# HLK-7621-ALL-KIT-V2_4.net
KiCad netlist of a schematic drawn in Altium Designer
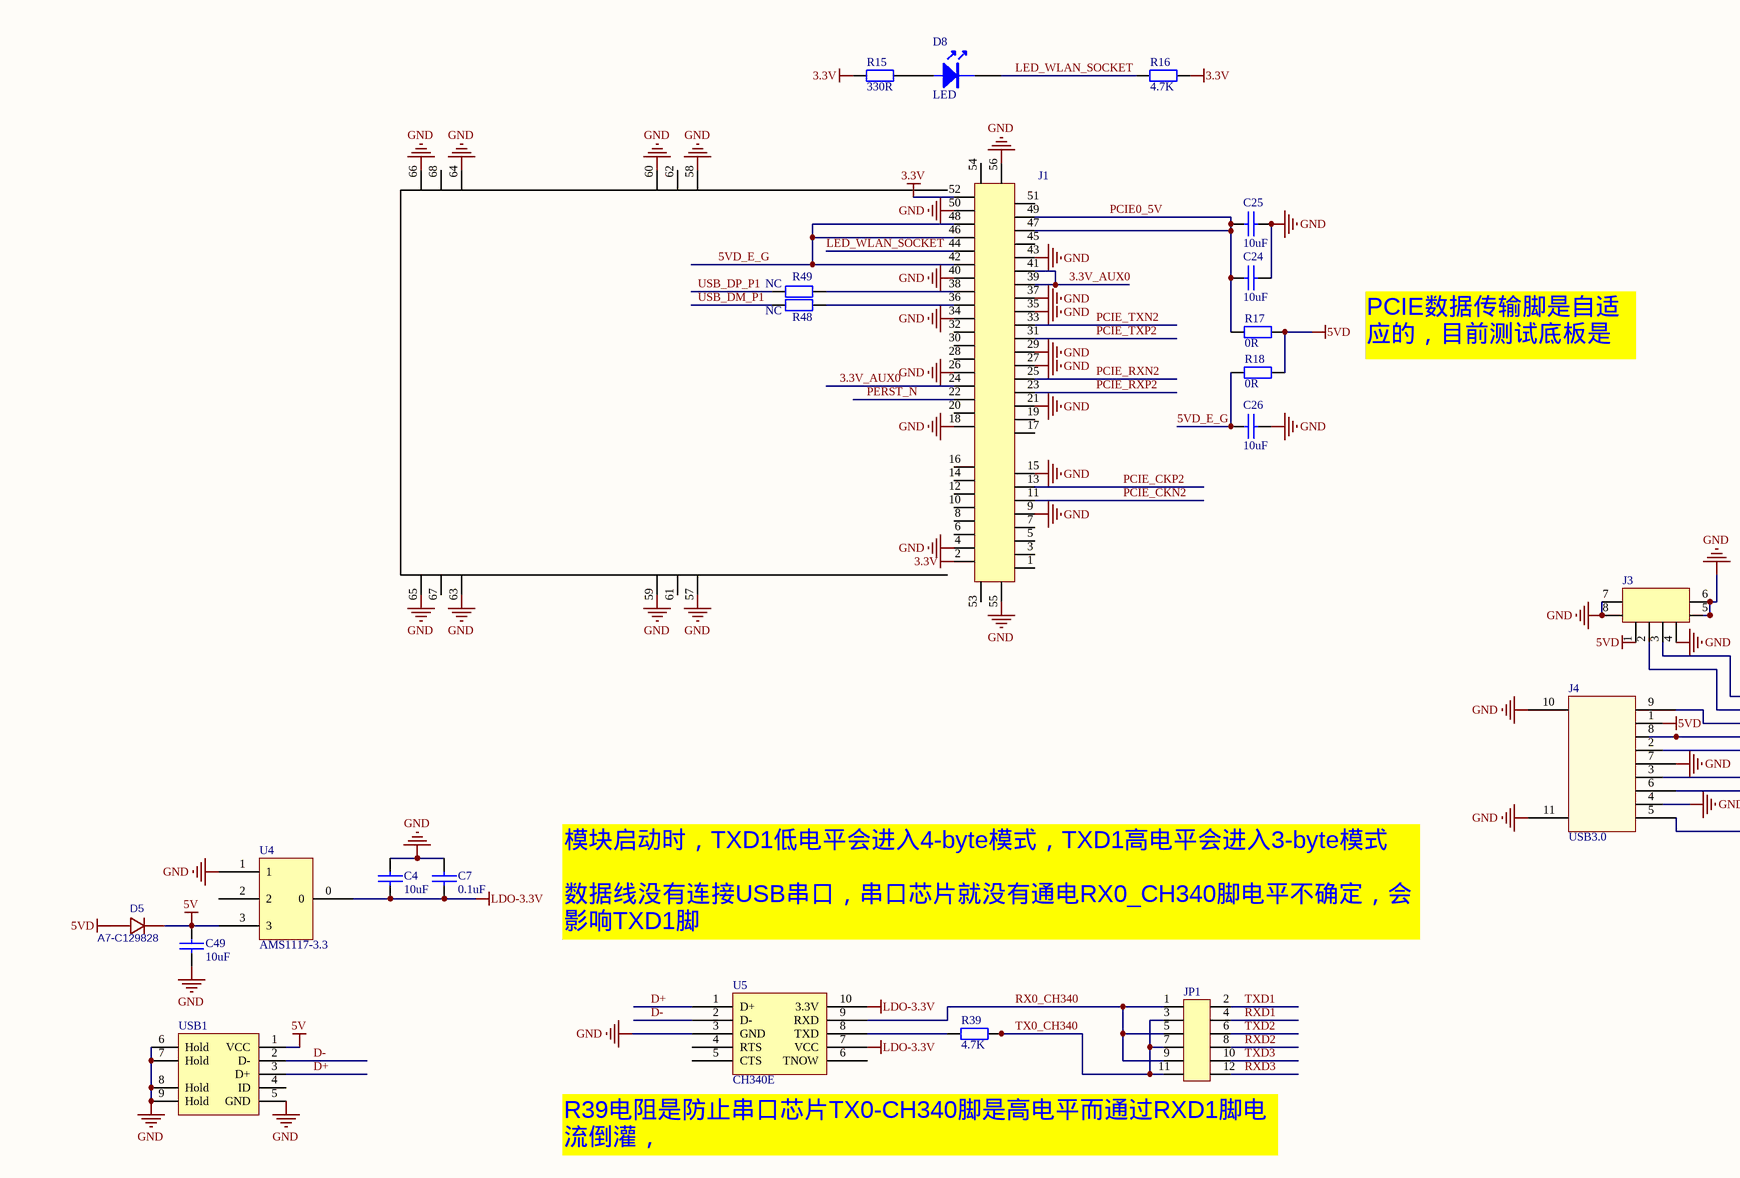
[diagram p0: HLK-7621-ALL-KIT-V2.4.SchDoc, top left]
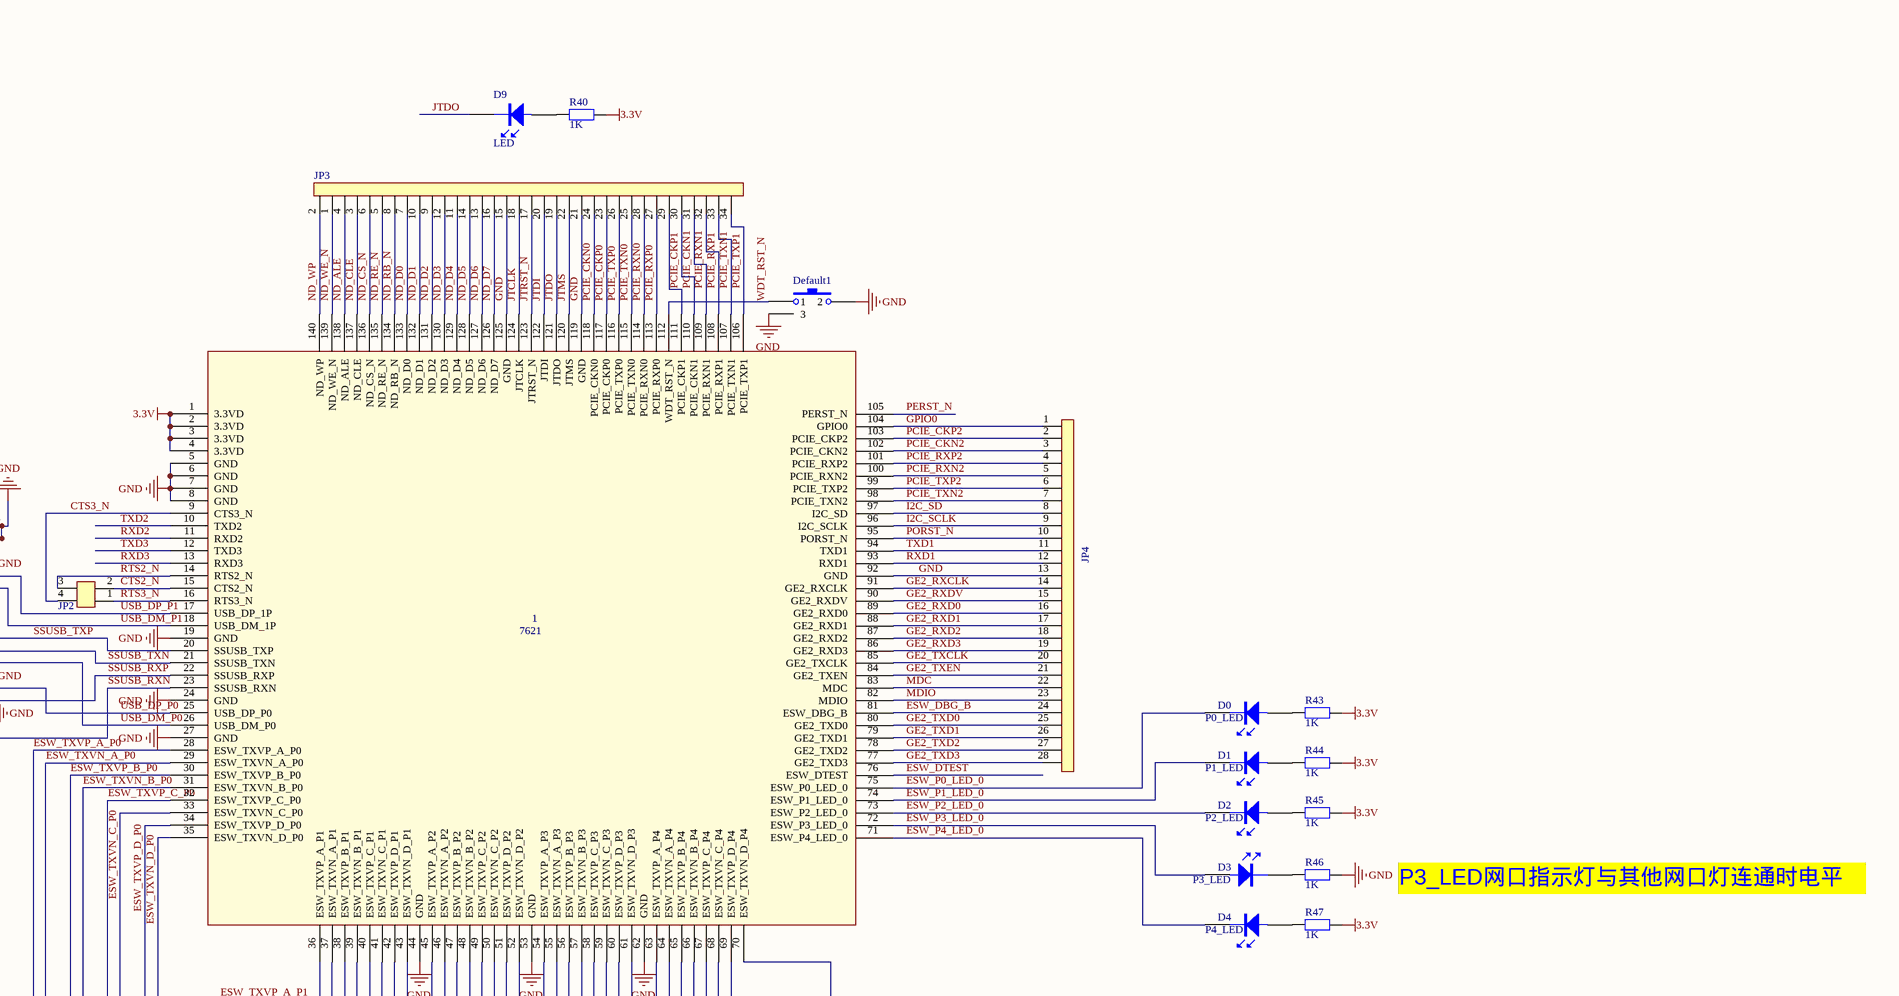
[diagram p1: HLK-7621-ALL-KIT-V2.4.SchDoc, top right]
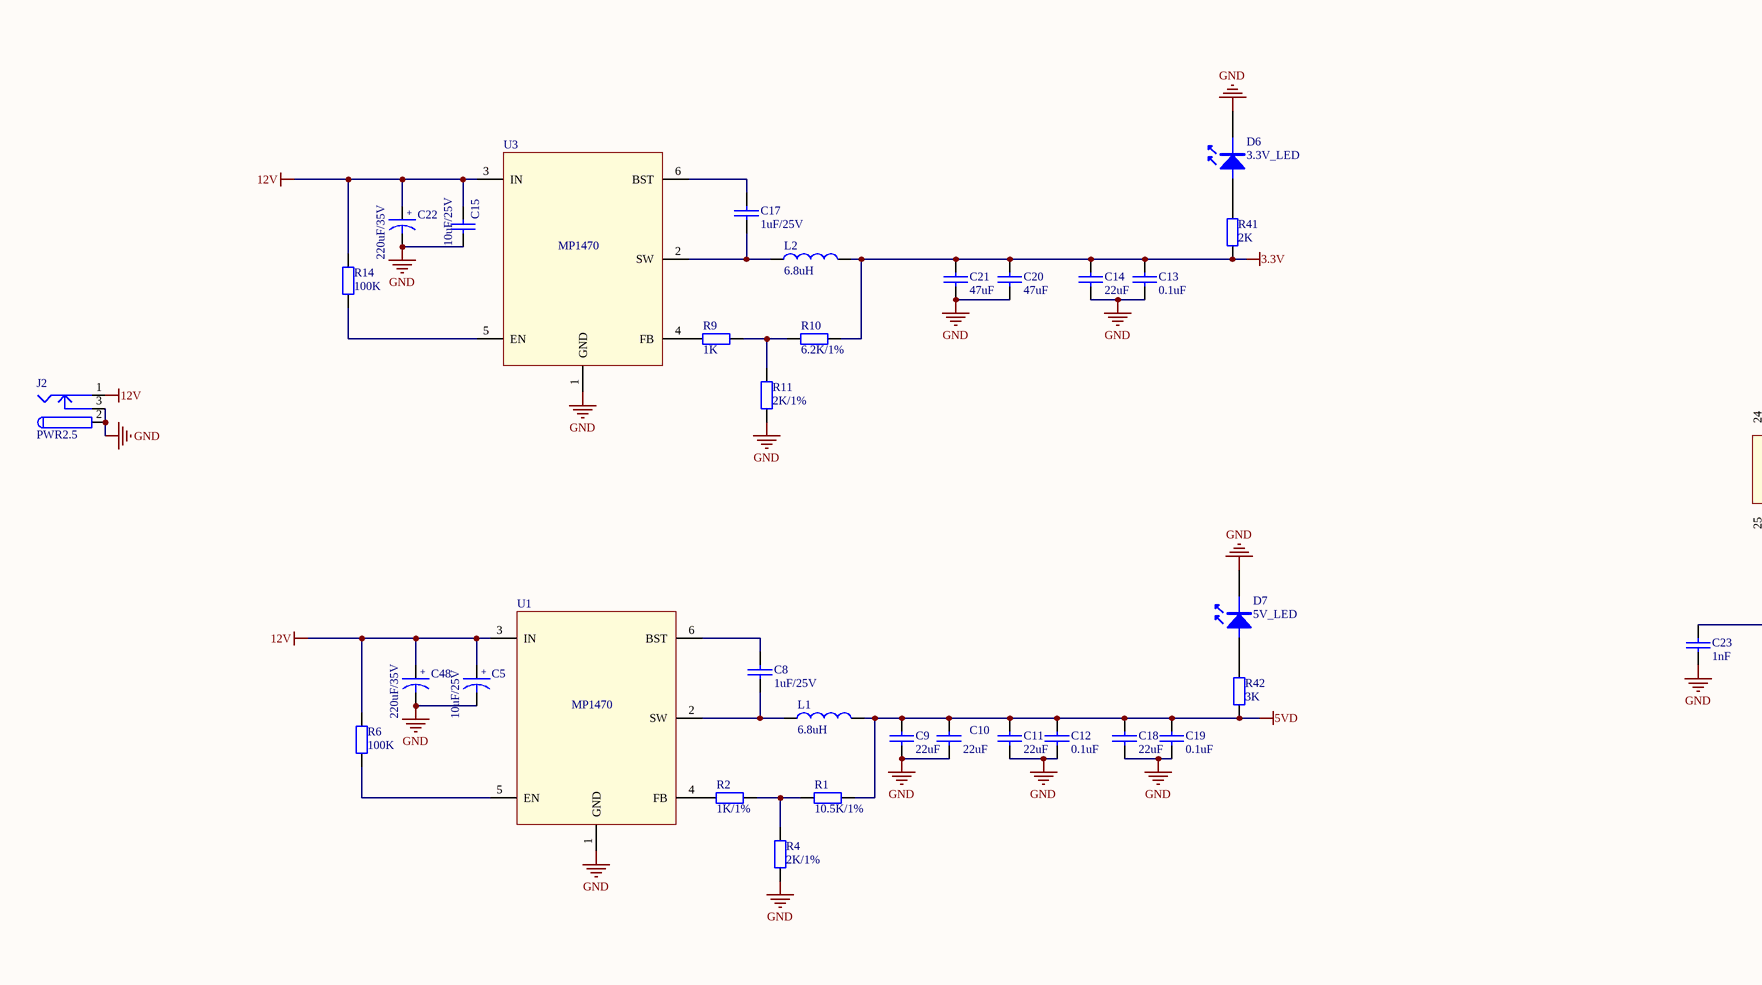
[diagram p2: HLK-7621-ALL-KIT-V2.4.SchDoc, bottom left]
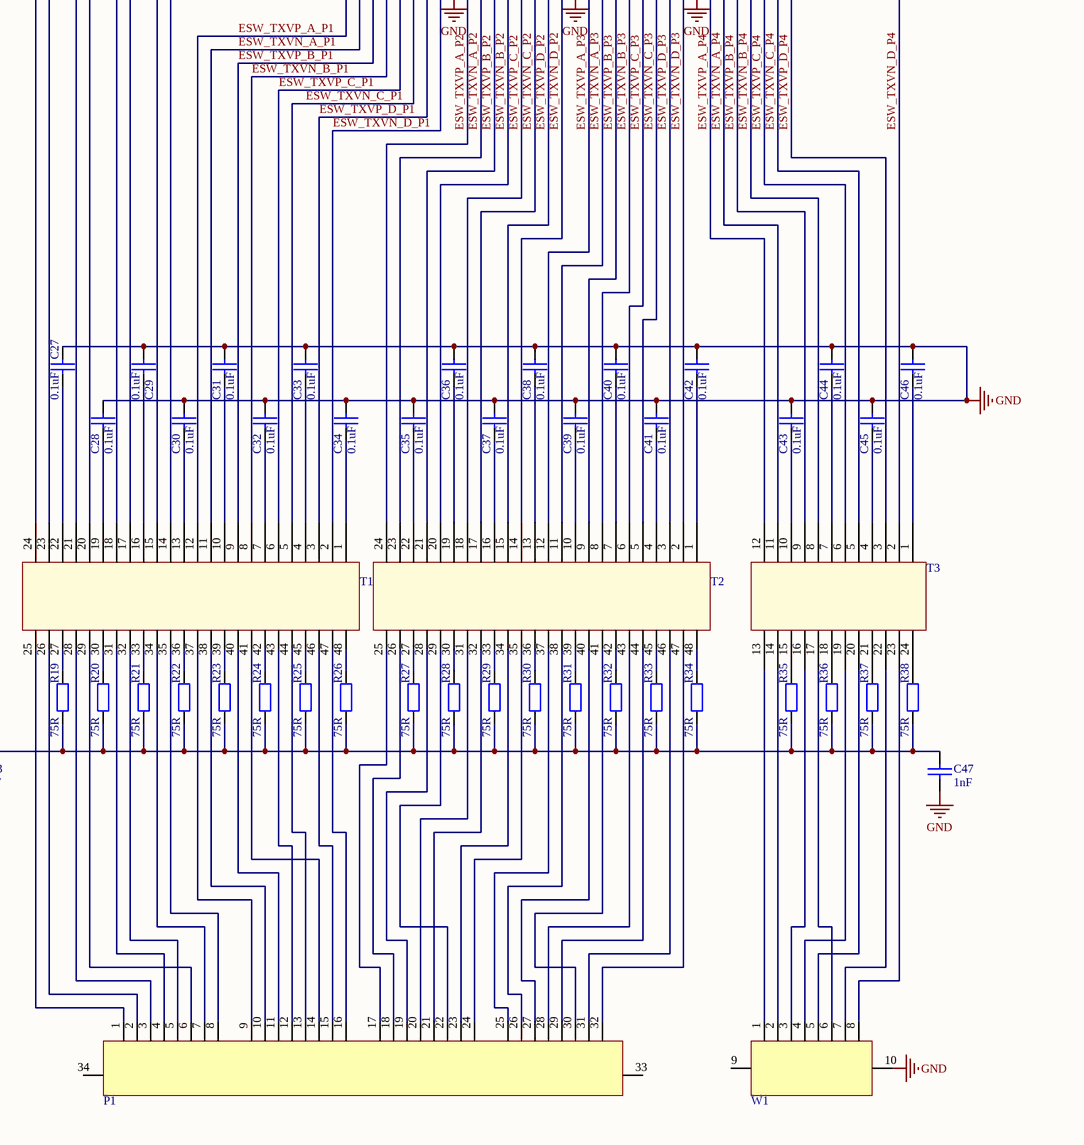
[diagram p3: HLK-7621-ALL-KIT-V2.4.SchDoc, bottom right]

(export (version "E")
  (design (tool "Eeschema 10.0.6"))
  (components
    (comp (ref "1") (value "7621") (footprint "HLK-7621") (libsource (lib "Schlib1") (part "7621")))
    (comp (ref "C4")
      (value "10uF")
      (footprint "0603")
      (description "Capacitor")
      (libsource (lib "*") (part "CAP"))
    )
    (comp (ref "C5")
      (value "10uF/25V")
      (footprint "L0805")
      (description "Capacitor")
      (libsource (lib "Miscellaneous Devices") (part "CAPACITOR POL"))
    )
    (comp (ref "C7")
      (value "0.1uF")
      (footprint "0603")
      (description "Capacitor")
      (libsource (lib "*") (part "CAP"))
    )
    (comp (ref "C8")
      (value "1uF/25V")
      (footprint "0603")
      (description "Capacitor")
      (libsource (lib "*") (part "CAP"))
    )
    (comp (ref "C9")
      (value "22uF")
      (footprint "0603")
      (description "Capacitor")
      (libsource (lib "*") (part "CAP"))
    )
    (comp (ref "C10")
      (value "22uF")
      (footprint "0603")
      (description "Capacitor")
      (libsource (lib "*") (part "CAP"))
    )
    (comp (ref "C11")
      (value "22uF")
      (footprint "0603")
      (description "Capacitor")
      (libsource (lib "*") (part "CAP"))
    )
    (comp (ref "C12")
      (value "0.1uF")
      (footprint "0603")
      (description "Capacitor")
      (libsource (lib "*") (part "CAP"))
    )
    (comp (ref "C13")
      (value "0.1uF")
      (footprint "0603")
      (description "Capacitor")
      (libsource (lib "*") (part "CAP"))
    )
    (comp (ref "C14")
      (value "22uF")
      (footprint "0603")
      (description "Capacitor")
      (libsource (lib "*") (part "CAP"))
    )
    (comp (ref "C15")
      (value "10uF/25V")
      (footprint "L0805")
      (description "Capacitor")
      (libsource (lib "*") (part "CAP"))
    )
    (comp (ref "C17")
      (value "1uF/25V")
      (footprint "0603")
      (description "Capacitor")
      (libsource (lib "*") (part "CAP"))
    )
    (comp (ref "C18")
      (value "22uF")
      (footprint "0603")
      (description "Capacitor")
      (libsource (lib "*") (part "CAP"))
    )
    (comp (ref "C19")
      (value "0.1uF")
      (footprint "0603")
      (description "Capacitor")
      (libsource (lib "*") (part "CAP"))
    )
    (comp (ref "C20")
      (value "47uF")
      (footprint "0603")
      (description "Capacitor")
      (libsource (lib "*") (part "CAP"))
    )
    (comp (ref "C21")
      (value "47uF")
      (footprint "0603")
      (description "Capacitor")
      (libsource (lib "*") (part "CAP"))
    )
    (comp (ref "C22")
      (value "220uF/35V")
      (footprint "CAP_SMT_8*10.5")
      (description "Capacitor")
      (libsource (lib "Miscellaneous Devices") (part "CAPACITOR POL"))
    )
    (comp (ref "C23")
      (value "1nF")
      (footprint "C1206")
      (description "Capacitor")
      (libsource (lib "*") (part "CAP"))
    )
    (comp (ref "C24")
      (value "10uF")
      (footprint "C1206")
      (description "Capacitor")
      (libsource (lib "*") (part "CAP"))
    )
    (comp (ref "C25")
      (value "10uF")
      (footprint "C1206")
      (description "Capacitor")
      (libsource (lib "*") (part "CAP"))
    )
    (comp (ref "C26")
      (value "10uF")
      (footprint "C1206")
      (description "Capacitor")
      (libsource (lib "*") (part "CAP"))
    )
    (comp (ref "C27")
      (value "0.1uF")
      (footprint "C0402")
      (description "Capacitor")
      (libsource (lib "*") (part "CAP"))
    )
    (comp (ref "C28")
      (value "0.1uF")
      (footprint "C0402")
      (description "Capacitor")
      (libsource (lib "*") (part "CAP"))
    )
    (comp (ref "C29")
      (value "0.1uF")
      (footprint "C0402")
      (description "Capacitor")
      (libsource (lib "*") (part "CAP"))
    )
    (comp (ref "C30")
      (value "0.1uF")
      (footprint "C0402")
      (description "Capacitor")
      (libsource (lib "*") (part "CAP"))
    )
    (comp (ref "C31")
      (value "0.1uF")
      (footprint "C0402")
      (description "Capacitor")
      (libsource (lib "*") (part "CAP"))
    )
    (comp (ref "C32")
      (value "0.1uF")
      (footprint "C0402")
      (description "Capacitor")
      (libsource (lib "*") (part "CAP"))
    )
    (comp (ref "C33")
      (value "0.1uF")
      (footprint "C0402")
      (description "Capacitor")
      (libsource (lib "*") (part "CAP"))
    )
    (comp (ref "C34")
      (value "0.1uF")
      (footprint "C0402")
      (description "Capacitor")
      (libsource (lib "*") (part "CAP"))
    )
    (comp (ref "C35")
      (value "0.1uF")
      (footprint "C0402")
      (description "Capacitor")
      (libsource (lib "*") (part "CAP"))
    )
    (comp (ref "C36")
      (value "0.1uF")
      (footprint "C0402")
      (description "Capacitor")
      (libsource (lib "*") (part "CAP"))
    )
    (comp (ref "C37")
      (value "0.1uF")
      (footprint "C0402")
      (description "Capacitor")
      (libsource (lib "*") (part "CAP"))
    )
    (comp (ref "C38")
      (value "0.1uF")
      (footprint "C0402")
      (description "Capacitor")
      (libsource (lib "*") (part "CAP"))
    )
    (comp (ref "C39")
      (value "0.1uF")
      (footprint "C0402")
      (description "Capacitor")
      (libsource (lib "*") (part "CAP"))
    )
    (comp (ref "C40")
      (value "0.1uF")
      (footprint "C0402")
      (description "Capacitor")
      (libsource (lib "*") (part "CAP"))
    )
    (comp (ref "C41")
      (value "0.1uF")
      (footprint "C0402")
      (description "Capacitor")
      (libsource (lib "*") (part "CAP"))
    )
    (comp (ref "C42")
      (value "0.1uF")
      (footprint "C0402")
      (description "Capacitor")
      (libsource (lib "*") (part "CAP"))
    )
    (comp (ref "C43")
      (value "0.1uF")
      (footprint "C0402")
      (description "Capacitor")
      (libsource (lib "*") (part "CAP"))
    )
    (comp (ref "C44")
      (value "0.1uF")
      (footprint "C0402")
      (description "Capacitor")
      (libsource (lib "*") (part "CAP"))
    )
    (comp (ref "C45")
      (value "0.1uF")
      (footprint "C0402")
      (description "Capacitor")
      (libsource (lib "*") (part "CAP"))
    )
    (comp (ref "C46")
      (value "0.1uF")
      (footprint "C0402")
      (description "Capacitor")
      (libsource (lib "*") (part "CAP"))
    )
    (comp (ref "C47")
      (value "1nF")
      (footprint "C1206")
      (description "Capacitor")
      (libsource (lib "*") (part "CAP"))
    )
    (comp (ref "C48")
      (value "220uF/35V")
      (footprint "CAP_SMT_8*10.5")
      (description "Capacitor")
      (libsource (lib "Miscellaneous Devices") (part "CAPACITOR POL"))
    )
    (comp (ref "C49")
      (value "10uF")
      (footprint "0603")
      (description "Capacitor")
      (libsource (lib "*") (part "CAP"))
    )
    (comp (ref "D0") (value "P0_LED") (footprint "0603LED") (libsource (lib "*") (part "LED")))
    (comp (ref "D1") (value "P1_LED") (footprint "0603LED") (libsource (lib "*") (part "LED")))
    (comp (ref "D2") (value "P2_LED") (footprint "0603LED") (libsource (lib "*") (part "LED")))
    (comp (ref "D3") (value "P3_LED") (footprint "0603LED") (libsource (lib "*") (part "LED")))
    (comp (ref "D4") (value "P4_LED") (footprint "0603LED") (libsource (lib "*") (part "LED")))
    (comp (ref "D5")
      (value "A7-C129828")
      (footprint "SOD-123F_L2.8-W1.8-LS3.7-RD")
      (fields (field (name "BOM_SUPPLIER PART") "C129828") (field (name "CONTRIBUTOR") "LCSC"))
      (libsource (lib "altium-import") (part "root_2_A7-C129828_"))
    )
    (comp (ref "D6") (value "3.3V_LED") (footprint "0603LED") (libsource (lib "*") (part "LED")))
    (comp (ref "D7") (value "5V_LED") (footprint "0603LED") (libsource (lib "*") (part "LED")))
    (comp (ref "D8") (value "LED") (footprint "0603LED") (libsource (lib "") (part "LED_1")))
    (comp (ref "D9") (value "LED") (footprint "0603LED") (libsource (lib "*") (part "LED")))
    (comp (ref "Default1")
      (value "SW-PB")
      (footprint "K5")
      (description "Switch")
      (fields (field (name "PUBLISHER") "Altium Limited"))
      (libsource (lib "Miscellaneous Devices") (part "SW-PB"))
    )
    (comp (ref "J1")
      (value "~")
      (footprint "CONSG/54/MINICARD/AS0B22-S68-7F/HALF/FUL")
      (libsource (lib "") (part "Component_1_2"))
    )
    (comp (ref "J2")
      (value "PWR2.5")
      (description "Low Voltage Power Supply Connector")
      (fields (field (name "PUBLISHER") "Altium Limited"))
      (libsource (lib "*") (part "PWR2.5"))
    )
    (comp (ref "J3") (value "~") (libsource (lib "") (part "2_1")))
    (comp (ref "J4") (value "USB3.0") (libsource (lib "Schlib1") (part "USB3.0/9P/DIP/MAINSUPER")))
    (comp (ref "JP1") (value "~") (footprint "HDR2X6") (libsource (lib "Schlib1") (part "Component_1")))
    (comp (ref "JP2") (value "~") (footprint "HDR2X2") (libsource (lib "") (part "2_2")))
    (comp (ref "JP3") (value "~") (footprint "HDR2X17") (libsource (lib "Schlib1") (part "2")))
    (comp (ref "JP4") (value "2") (footprint "HDR2X17") (libsource (lib "") (part "2_3")))
    (comp (ref "L1")
      (value "6.8uH")
      (footprint "4.7uH SMD,5.8x5.2x4.5mm")
      (libsource (lib "ARM9") (part "INDUCTOR1"))
    )
    (comp (ref "L2")
      (value "6.8uH")
      (footprint "4.7uH SMD,5.8x5.2x4.5mm")
      (libsource (lib "ARM9") (part "INDUCTOR1"))
    )
    (comp (ref "P1")
      (value "Component_2")
      (footprint "PHJ8X4_N")
      (libsource (lib "Schlib1") (part "Component_2"))
    )
    (comp (ref "R1")
      (value "10.5K/1%")
      (footprint "0603")
      (description "Resistor")
      (fields (field (name "PUBLISHER") "Altium Limited"))
      (libsource (lib "Miscellaneous Devices") (part "Res2"))
    )
    (comp (ref "R2")
      (value "1K/1%")
      (footprint "0603")
      (description "Resistor")
      (fields (field (name "PUBLISHER") "Altium Limited"))
      (libsource (lib "Miscellaneous Devices") (part "Res2"))
    )
    (comp (ref "R4")
      (value "2K/1%")
      (footprint "0603")
      (description "Resistor")
      (fields (field (name "PUBLISHER") "Altium Limited"))
      (libsource (lib "") (part "Res2_1"))
    )
    (comp (ref "R6")
      (value "100K")
      (footprint "0603")
      (description "Resistor")
      (fields (field (name "PUBLISHER") "Altium Limited"))
      (libsource (lib "") (part "Res2_1"))
    )
    (comp (ref "R9")
      (value "1K")
      (footprint "0603")
      (description "Resistor")
      (fields (field (name "PUBLISHER") "Altium Limited"))
      (libsource (lib "Miscellaneous Devices") (part "Res2"))
    )
    (comp (ref "R10")
      (value "6.2K/1%")
      (footprint "0603")
      (description "Resistor")
      (fields (field (name "PUBLISHER") "Altium Limited"))
      (libsource (lib "Miscellaneous Devices") (part "Res2"))
    )
    (comp (ref "R11")
      (value "2K/1%")
      (footprint "0603")
      (description "Resistor")
      (fields (field (name "PUBLISHER") "Altium Limited"))
      (libsource (lib "") (part "Res2_1"))
    )
    (comp (ref "R14")
      (value "100K")
      (footprint "0603")
      (description "Resistor")
      (fields (field (name "PUBLISHER") "Altium Limited"))
      (libsource (lib "") (part "Res2_1"))
    )
    (comp (ref "R15")
      (value "330R")
      (footprint "0603")
      (description "Resistor")
      (fields (field (name "PUBLISHER") "Altium Limited"))
      (libsource (lib "Miscellaneous Devices") (part "Res2"))
    )
    (comp (ref "R16")
      (value "4.7K")
      (footprint "0603")
      (description "Resistor")
      (fields (field (name "PUBLISHER") "Altium Limited"))
      (libsource (lib "Miscellaneous Devices") (part "Res2"))
    )
    (comp (ref "R17")
      (value "0R")
      (footprint "L0805")
      (description "Resistor")
      (fields (field (name "PUBLISHER") "Altium Limited"))
      (libsource (lib "") (part "Res2_2"))
    )
    (comp (ref "R18")
      (value "0R")
      (footprint "R1206")
      (description "Resistor")
      (fields (field (name "PUBLISHER") "Altium Limited"))
      (libsource (lib "Miscellaneous Devices") (part "Res2"))
    )
    (comp (ref "R19")
      (value "75R")
      (footprint "R0402")
      (description "Resistor")
      (fields (field (name "PUBLISHER") "Altium Limited"))
      (libsource (lib "Schlib1") (part "Res2"))
    )
    (comp (ref "R20")
      (value "75R")
      (footprint "R0402")
      (description "Resistor")
      (fields (field (name "PUBLISHER") "Altium Limited"))
      (libsource (lib "Schlib1") (part "Res2"))
    )
    (comp (ref "R21")
      (value "75R")
      (footprint "R0402")
      (description "Resistor")
      (fields (field (name "PUBLISHER") "Altium Limited"))
      (libsource (lib "Schlib1") (part "Res2"))
    )
    (comp (ref "R22")
      (value "75R")
      (footprint "R0402")
      (description "Resistor")
      (fields (field (name "PUBLISHER") "Altium Limited"))
      (libsource (lib "Schlib1") (part "Res2"))
    )
    (comp (ref "R23")
      (value "75R")
      (footprint "R0402")
      (description "Resistor")
      (fields (field (name "PUBLISHER") "Altium Limited"))
      (libsource (lib "Schlib1") (part "Res2"))
    )
    (comp (ref "R24")
      (value "75R")
      (footprint "R0402")
      (description "Resistor")
      (fields (field (name "PUBLISHER") "Altium Limited"))
      (libsource (lib "Schlib1") (part "Res2"))
    )
    (comp (ref "R25")
      (value "75R")
      (footprint "R0402")
      (description "Resistor")
      (fields (field (name "PUBLISHER") "Altium Limited"))
      (libsource (lib "Schlib1") (part "Res2"))
    )
    (comp (ref "R26")
      (value "75R")
      (footprint "R0402")
      (description "Resistor")
      (fields (field (name "PUBLISHER") "Altium Limited"))
      (libsource (lib "Schlib1") (part "Res2"))
    )
    (comp (ref "R27")
      (value "75R")
      (footprint "R0402")
      (description "Resistor")
      (fields (field (name "PUBLISHER") "Altium Limited"))
      (libsource (lib "Schlib1") (part "Res2"))
    )
    (comp (ref "R28")
      (value "75R")
      (footprint "R0402")
      (description "Resistor")
      (fields (field (name "PUBLISHER") "Altium Limited"))
      (libsource (lib "Schlib1") (part "Res2"))
    )
    (comp (ref "R29")
      (value "75R")
      (footprint "R0402")
      (description "Resistor")
      (fields (field (name "PUBLISHER") "Altium Limited"))
      (libsource (lib "Schlib1") (part "Res2"))
    )
    (comp (ref "R30")
      (value "75R")
      (footprint "R0402")
      (description "Resistor")
      (fields (field (name "PUBLISHER") "Altium Limited"))
      (libsource (lib "Schlib1") (part "Res2"))
    )
    (comp (ref "R31")
      (value "75R")
      (footprint "R0402")
      (description "Resistor")
      (fields (field (name "PUBLISHER") "Altium Limited"))
      (libsource (lib "Schlib1") (part "Res2"))
    )
    (comp (ref "R32")
      (value "75R")
      (footprint "R0402")
      (description "Resistor")
      (fields (field (name "PUBLISHER") "Altium Limited"))
      (libsource (lib "Schlib1") (part "Res2"))
    )
    (comp (ref "R33")
      (value "75R")
      (footprint "R0402")
      (description "Resistor")
      (fields (field (name "PUBLISHER") "Altium Limited"))
      (libsource (lib "Schlib1") (part "Res2"))
    )
    (comp (ref "R34")
      (value "75R")
      (footprint "R0402")
      (description "Resistor")
      (fields (field (name "PUBLISHER") "Altium Limited"))
      (libsource (lib "Schlib1") (part "Res2"))
    )
    (comp (ref "R35")
      (value "75R")
      (footprint "R0402")
      (description "Resistor")
      (fields (field (name "PUBLISHER") "Altium Limited"))
      (libsource (lib "Schlib1") (part "Res2"))
    )
    (comp (ref "R36")
      (value "75R")
      (footprint "R0402")
      (description "Resistor")
      (fields (field (name "PUBLISHER") "Altium Limited"))
      (libsource (lib "Schlib1") (part "Res2"))
    )
    (comp (ref "R37")
      (value "75R")
      (footprint "R0402")
      (description "Resistor")
      (fields (field (name "PUBLISHER") "Altium Limited"))
      (libsource (lib "Schlib1") (part "Res2"))
    )
    (comp (ref "R38")
      (value "75R")
      (footprint "R0402")
      (description "Resistor")
      (fields (field (name "PUBLISHER") "Altium Limited"))
      (libsource (lib "Schlib1") (part "Res2"))
    )
    (comp (ref "R39")
      (value "4.7K")
      (footprint "0603")
      (description "Resistor")
      (fields (field (name "PUBLISHER") "Altium Limited"))
      (libsource (lib "") (part "Res2_2"))
    )
    (comp (ref "R40")
      (value "1K")
      (footprint "0603")
      (description "Resistor")
      (fields (field (name "PUBLISHER") "Altium Limited"))
      (libsource (lib "Miscellaneous Devices") (part "Res2"))
    )
    (comp (ref "R41")
      (value "2K")
      (footprint "0603")
      (description "Resistor")
      (fields (field (name "PUBLISHER") "Altium Limited"))
      (libsource (lib "") (part "Res2_1"))
    )
    (comp (ref "R42")
      (value "3K")
      (footprint "0603")
      (description "Resistor")
      (fields (field (name "PUBLISHER") "Altium Limited"))
      (libsource (lib "") (part "Res2_1"))
    )
    (comp (ref "R43")
      (value "1K")
      (footprint "0603")
      (description "Resistor")
      (fields (field (name "PUBLISHER") "Altium Limited"))
      (libsource (lib "Miscellaneous Devices") (part "Res2"))
    )
    (comp (ref "R44")
      (value "1K")
      (footprint "0603")
      (description "Resistor")
      (fields (field (name "PUBLISHER") "Altium Limited"))
      (libsource (lib "Miscellaneous Devices") (part "Res2"))
    )
    (comp (ref "R45")
      (value "1K")
      (footprint "0603")
      (description "Resistor")
      (fields (field (name "PUBLISHER") "Altium Limited"))
      (libsource (lib "Miscellaneous Devices") (part "Res2"))
    )
    (comp (ref "R46")
      (value "1K")
      (footprint "0603")
      (description "Resistor")
      (fields (field (name "PUBLISHER") "Altium Limited"))
      (libsource (lib "Miscellaneous Devices") (part "Res2"))
    )
    (comp (ref "R47")
      (value "1K")
      (footprint "0603")
      (description "Resistor")
      (fields (field (name "PUBLISHER") "Altium Limited"))
      (libsource (lib "Miscellaneous Devices") (part "Res2"))
    )
    (comp (ref "R48")
      (value "NC")
      (footprint "0603")
      (description "Resistor")
      (fields (field (name "PUBLISHER") "Altium Limited"))
      (libsource (lib "Miscellaneous Devices") (part "Res2"))
    )
    (comp (ref "R49")
      (value "NC")
      (footprint "0603")
      (description "Resistor")
      (fields (field (name "PUBLISHER") "Altium Limited"))
      (libsource (lib "Miscellaneous Devices") (part "Res2"))
    )
    (comp (ref "T1")
      (value "HN4824CG")
      (footprint "TRANSFORMER/48P/SMD/GS5014LF")
      (libsource (lib "Schlib1") (part "TRANSFORMER/24P/SMD/HN2429CG"))
    )
    (comp (ref "T2")
      (value "HN4824CG")
      (footprint "TRANSFORMER/48P/SMD/GS5014LF")
      (libsource (lib "Schlib1") (part "TRANSFORMER/24P/SMD/HN2429CG"))
    )
    (comp (ref "T3")
      (value "HN2409CG")
      (footprint "TRANSFORMER/24P/SMD/HN2429CG")
      (libsource (lib "") (part "TRANSFORMER/24P/SMD/HN2429CG_1"))
    )
    (comp (ref "U1") (value "MP1470") (footprint "MP1470") (libsource (lib "原理图库") (part "MP1470")))
    (comp (ref "U3") (value "MP1470") (footprint "MP1470") (libsource (lib "原理图库") (part "MP1470")))
    (comp (ref "U4") (value "AMS1117-3.3") (footprint "1117") (libsource (lib "") (part "Component_1_1")))
    (comp (ref "U5") (value "CH340E") (footprint "MSOP-10") (libsource (lib "Schlib1") (part "CH340E")))
    (comp (ref "USB1") (value "USB1") (libsource (lib "Schlib1") (part "USB-B")))
    (comp (ref "W1")
      (value "Component_3")
      (footprint "PCBComponent_1")
      (libsource (lib "Schlib1") (part "Component_3"))
    )
  )
  (nets
    (net (code "1") (name "/3.3V_AUX0") (class "Default")
      (node (ref "J1") (pin "24") (pinfunction "24_24") (pintype "passive"))
      (node (ref "J1") (pin "39") (pinfunction "39_39") (pintype "passive"))
      (node (ref "J1") (pin "41") (pinfunction "41_41") (pintype "passive"))
    )
    (net (code "2") (name "/5VD_E_G") (class "Default")
      (node (ref "C26") (pin "1") (pinfunction "1_1") (pintype "passive"))
      (node (ref "J1") (pin "42") (pinfunction "42_42") (pintype "passive"))
      (node (ref "J1") (pin "46") (pinfunction "46_46") (pintype "passive"))
      (node (ref "J1") (pin "48") (pinfunction "48_48") (pintype "passive"))
      (node (ref "R18") (pin "2") (pinfunction "2_2") (pintype "passive"))
    )
    (net (code "3") (name "/CTS2_N") (class "Default")
      (node (ref "1") (pin "15") (pinfunction "CTS2_N_15") (pintype "passive"))
      (node (ref "JP2") (pin "2") (pinfunction "2_2") (pintype "passive"))
    )
    (net (code "4") (name "/CTS3_N") (class "Default")
      (node (ref "1") (pin "9") (pinfunction "CTS3_N_9") (pintype "passive"))
      (node (ref "JP2") (pin "4") (pinfunction "4_4") (pintype "passive"))
    )
    (net (code "5") (name "/D+") (class "Default")
      (node (ref "U5") (pin "1") (pinfunction "D+_1") (pintype "passive"))
      (node (ref "USB1") (pin "3") (pinfunction "D+_3") (pintype "passive"))
    )
    (net (code "6") (name "/D-") (class "Default")
      (node (ref "U5") (pin "2") (pinfunction "D-_2") (pintype "passive"))
      (node (ref "USB1") (pin "2") (pinfunction "D-_2") (pintype "passive"))
    )
    (net (code "7") (name "/ESW_DBG_B") (class "Default")
      (node (ref "1") (pin "81") (pinfunction "ESW_DBG_B_81") (pintype "passive"))
      (node (ref "JP4") (pin "24") (pinfunction "24_24") (pintype "passive"))
    )
    (net (code "8") (name "/ESW_DTEST") (class "Default")
      (node (ref "1") (pin "76") (pinfunction "ESW_DTEST_76") (pintype "passive"))
    )
    (net (code "9") (name "/ESW_P0_LED_0") (class "Default")
      (node (ref "1") (pin "75") (pinfunction "ESW_P0_LED_0_75") (pintype "passive"))
      (node (ref "D0") (pin "2") (pinfunction "2_2") (pintype "passive"))
    )
    (net (code "10") (name "/ESW_P1_LED_0") (class "Default")
      (node (ref "1") (pin "74") (pinfunction "ESW_P1_LED_0_74") (pintype "passive"))
      (node (ref "D1") (pin "2") (pinfunction "2_2") (pintype "passive"))
    )
    (net (code "11") (name "/ESW_P2_LED_0") (class "Default")
      (node (ref "1") (pin "73") (pinfunction "ESW_P2_LED_0_73") (pintype "passive"))
      (node (ref "D2") (pin "2") (pinfunction "2_2") (pintype "passive"))
    )
    (net (code "12") (name "/ESW_P3_LED_0") (class "Default")
      (node (ref "1") (pin "72") (pinfunction "ESW_P3_LED_0_72") (pintype "passive"))
      (node (ref "D3") (pin "1") (pinfunction "1_1") (pintype "passive"))
    )
    (net (code "13") (name "/ESW_P4_LED_0") (class "Default")
      (node (ref "1") (pin "71") (pinfunction "ESW_P4_LED_0_71") (pintype "passive"))
      (node (ref "D4") (pin "2") (pinfunction "2_2") (pintype "passive"))
    )
    (net (code "14") (name "/ESW_TXVN_A_P0") (class "Default")
      (node (ref "1") (pin "29") (pinfunction "ESW_TXVN_A_P0_29") (pintype "passive"))
      (node (ref "T1") (pin "23") (pinfunction "23_23") (pintype "passive"))
    )
    (net (code "15") (name "/ESW_TXVN_A_P1") (class "Default")
      (node (ref "1") (pin "37") (pinfunction "ESW_TXVN_A_P1_37") (pintype "passive"))
      (node (ref "T1") (pin "11") (pinfunction "11_11") (pintype "passive"))
    )
    (net (code "16") (name "/ESW_TXVN_A_P2") (class "Default")
      (node (ref "1") (pin "46") (pinfunction "ESW_TXVN_A_P2_46") (pintype "passive"))
      (node (ref "T2") (pin "23") (pinfunction "23_23") (pintype "passive"))
    )
    (net (code "17") (name "/ESW_TXVN_A_P3") (class "Default")
      (node (ref "1") (pin "55") (pinfunction "ESW_TXVN_A_P3_55") (pintype "passive"))
      (node (ref "T2") (pin "11") (pinfunction "11_11") (pintype "passive"))
    )
    (net (code "18") (name "/ESW_TXVN_A_P4") (class "Default")
      (node (ref "1") (pin "64") (pinfunction "ESW_TXVN_A_P4_64") (pintype "passive"))
      (node (ref "T3") (pin "11") (pinfunction "11_11") (pintype "passive"))
    )
    (net (code "19") (name "/ESW_TXVN_B_P0") (class "Default")
      (node (ref "1") (pin "31") (pinfunction "ESW_TXVN_B_P0_31") (pintype "passive"))
      (node (ref "T1") (pin "20") (pinfunction "20_20") (pintype "passive"))
    )
    (net (code "20") (name "/ESW_TXVN_B_P1") (class "Default")
      (node (ref "1") (pin "39") (pinfunction "ESW_TXVN_B_P1_39") (pintype "passive"))
      (node (ref "T1") (pin "8") (pinfunction "8_8") (pintype "passive"))
    )
    (net (code "21") (name "/ESW_TXVN_B_P2") (class "Default")
      (node (ref "1") (pin "48") (pinfunction "ESW_TXVN_B_P2_48") (pintype "passive"))
      (node (ref "T2") (pin "20") (pinfunction "20_20") (pintype "passive"))
    )
    (net (code "22") (name "/ESW_TXVN_B_P3") (class "Default")
      (node (ref "1") (pin "57") (pinfunction "ESW_TXVN_B_P3_57") (pintype "passive"))
      (node (ref "T2") (pin "8") (pinfunction "8_8") (pintype "passive"))
    )
    (net (code "23") (name "/ESW_TXVN_B_P4") (class "Default")
      (node (ref "1") (pin "66") (pinfunction "ESW_TXVN_B_P4_66") (pintype "passive"))
      (node (ref "T3") (pin "8") (pinfunction "8_8") (pintype "passive"))
    )
    (net (code "24") (name "/ESW_TXVN_C_P0") (class "Default")
      (node (ref "1") (pin "33") (pinfunction "ESW_TXVN_C_P0_33") (pintype "passive"))
      (node (ref "T1") (pin "17") (pinfunction "17_17") (pintype "passive"))
    )
    (net (code "25") (name "/ESW_TXVN_C_P1") (class "Default")
      (node (ref "1") (pin "41") (pinfunction "ESW_TXVN_C_P1_41") (pintype "passive"))
      (node (ref "T1") (pin "5") (pinfunction "5_5") (pintype "passive"))
    )
    (net (code "26") (name "/ESW_TXVN_C_P2") (class "Default")
      (node (ref "1") (pin "50") (pinfunction "ESW_TXVN_C_P2_50") (pintype "passive"))
      (node (ref "T2") (pin "17") (pinfunction "17_17") (pintype "passive"))
    )
    (net (code "27") (name "/ESW_TXVN_C_P3") (class "Default")
      (node (ref "1") (pin "59") (pinfunction "ESW_TXVN_C_P3_59") (pintype "passive"))
      (node (ref "T2") (pin "5") (pinfunction "5_5") (pintype "passive"))
    )
    (net (code "28") (name "/ESW_TXVN_C_P4") (class "Default")
      (node (ref "1") (pin "68") (pinfunction "ESW_TXVN_C_P4_68") (pintype "passive"))
      (node (ref "T3") (pin "5") (pinfunction "5_5") (pintype "passive"))
    )
    (net (code "29") (name "/ESW_TXVN_D_P0") (class "Default")
      (node (ref "1") (pin "35") (pinfunction "ESW_TXVN_D_P0_35") (pintype "passive"))
      (node (ref "T1") (pin "14") (pinfunction "14_14") (pintype "passive"))
    )
    (net (code "30") (name "/ESW_TXVN_D_P1") (class "Default")
      (node (ref "1") (pin "43") (pinfunction "ESW_TXVN_D_P1_43") (pintype "passive"))
      (node (ref "T1") (pin "2") (pinfunction "2_2") (pintype "passive"))
    )
    (net (code "31") (name "/ESW_TXVN_D_P2") (class "Default")
      (node (ref "1") (pin "52") (pinfunction "ESW_TXVN_D_P2_52") (pintype "passive"))
      (node (ref "T2") (pin "14") (pinfunction "14_14") (pintype "passive"))
    )
    (net (code "32") (name "/ESW_TXVN_D_P3") (class "Default")
      (node (ref "1") (pin "61") (pinfunction "ESW_TXVN_D_P3_61") (pintype "passive"))
      (node (ref "T2") (pin "2") (pinfunction "2_2") (pintype "passive"))
    )
    (net (code "33") (name "/ESW_TXVN_D_P4") (class "Default")
      (node (ref "1") (pin "70") (pinfunction "ESW_TXVN_D_P4_70") (pintype "passive"))
      (node (ref "T3") (pin "2") (pinfunction "2_2") (pintype "passive"))
    )
    (net (code "34") (name "/ESW_TXVP_A_P0") (class "Default")
      (node (ref "1") (pin "28") (pinfunction "ESW_TXVP_A_P0_28") (pintype "passive"))
      (node (ref "T1") (pin "24") (pinfunction "24_24") (pintype "passive"))
    )
    (net (code "35") (name "/ESW_TXVP_A_P1") (class "Default")
      (node (ref "1") (pin "36") (pinfunction "ESW_TXVP_A_P1_36") (pintype "passive"))
      (node (ref "T1") (pin "12") (pinfunction "12_12") (pintype "passive"))
    )
    (net (code "36") (name "/ESW_TXVP_A_P2") (class "Default")
      (node (ref "1") (pin "45") (pinfunction "ESW_TXVP_A_P2_45") (pintype "passive"))
      (node (ref "T2") (pin "24") (pinfunction "24_24") (pintype "passive"))
    )
    (net (code "37") (name "/ESW_TXVP_A_P3") (class "Default")
      (node (ref "1") (pin "54") (pinfunction "ESW_TXVP_A_P3_54") (pintype "passive"))
      (node (ref "T2") (pin "12") (pinfunction "12_12") (pintype "passive"))
    )
    (net (code "38") (name "/ESW_TXVP_A_P4") (class "Default")
      (node (ref "1") (pin "63") (pinfunction "ESW_TXVP_A_P4_63") (pintype "passive"))
      (node (ref "T3") (pin "12") (pinfunction "12_12") (pintype "passive"))
    )
    (net (code "39") (name "/ESW_TXVP_B_P0") (class "Default")
      (node (ref "1") (pin "30") (pinfunction "ESW_TXVP_B_P0_30") (pintype "passive"))
      (node (ref "T1") (pin "21") (pinfunction "21_21") (pintype "passive"))
    )
    (net (code "40") (name "/ESW_TXVP_B_P1") (class "Default")
      (node (ref "1") (pin "38") (pinfunction "ESW_TXVP_B_P1_38") (pintype "passive"))
      (node (ref "T1") (pin "9") (pinfunction "9_9") (pintype "passive"))
    )
    (net (code "41") (name "/ESW_TXVP_B_P2") (class "Default")
      (node (ref "1") (pin "47") (pinfunction "ESW_TXVP_B_P2_47") (pintype "passive"))
      (node (ref "T2") (pin "21") (pinfunction "21_21") (pintype "passive"))
    )
    (net (code "42") (name "/ESW_TXVP_B_P3") (class "Default")
      (node (ref "1") (pin "56") (pinfunction "ESW_TXVP_B_P3_56") (pintype "passive"))
      (node (ref "T2") (pin "9") (pinfunction "9_9") (pintype "passive"))
    )
    (net (code "43") (name "/ESW_TXVP_B_P4") (class "Default")
      (node (ref "1") (pin "65") (pinfunction "ESW_TXVP_B_P4_65") (pintype "passive"))
      (node (ref "T3") (pin "9") (pinfunction "9_9") (pintype "passive"))
    )
    (net (code "44") (name "/ESW_TXVP_C_P0") (class "Default")
      (node (ref "1") (pin "32") (pinfunction "ESW_TXVP_C_P0_32") (pintype "passive"))
      (node (ref "T1") (pin "18") (pinfunction "18_18") (pintype "passive"))
    )
    (net (code "45") (name "/ESW_TXVP_C_P1") (class "Default")
      (node (ref "1") (pin "40") (pinfunction "ESW_TXVP_C_P1_40") (pintype "passive"))
      (node (ref "T1") (pin "6") (pinfunction "6_6") (pintype "passive"))
    )
    (net (code "46") (name "/ESW_TXVP_C_P2") (class "Default")
      (node (ref "1") (pin "49") (pinfunction "ESW_TXVP_C_P2_49") (pintype "passive"))
      (node (ref "T2") (pin "18") (pinfunction "18_18") (pintype "passive"))
    )
    (net (code "47") (name "/ESW_TXVP_C_P3") (class "Default")
      (node (ref "1") (pin "58") (pinfunction "ESW_TXVP_C_P3_58") (pintype "passive"))
      (node (ref "T2") (pin "6") (pinfunction "6_6") (pintype "passive"))
    )
    (net (code "48") (name "/ESW_TXVP_C_P4") (class "Default")
      (node (ref "1") (pin "67") (pinfunction "ESW_TXVP_C_P4_67") (pintype "passive"))
      (node (ref "T3") (pin "6") (pinfunction "6_6") (pintype "passive"))
    )
    (net (code "49") (name "/ESW_TXVP_D_P0") (class "Default")
      (node (ref "1") (pin "34") (pinfunction "ESW_TXVP_D_P0_34") (pintype "passive"))
      (node (ref "T1") (pin "15") (pinfunction "15_15") (pintype "passive"))
    )
    (net (code "50") (name "/ESW_TXVP_D_P1") (class "Default")
      (node (ref "1") (pin "42") (pinfunction "ESW_TXVP_D_P1_42") (pintype "passive"))
      (node (ref "T1") (pin "3") (pinfunction "3_3") (pintype "passive"))
    )
    (net (code "51") (name "/ESW_TXVP_D_P2") (class "Default")
      (node (ref "1") (pin "51") (pinfunction "ESW_TXVP_D_P2_51") (pintype "passive"))
      (node (ref "T2") (pin "15") (pinfunction "15_15") (pintype "passive"))
    )
    (net (code "52") (name "/ESW_TXVP_D_P3") (class "Default")
      (node (ref "1") (pin "60") (pinfunction "ESW_TXVP_D_P3_60") (pintype "passive"))
      (node (ref "T2") (pin "3") (pinfunction "3_3") (pintype "passive"))
    )
    (net (code "53") (name "/ESW_TXVP_D_P4") (class "Default")
      (node (ref "1") (pin "69") (pinfunction "ESW_TXVP_D_P4_69") (pintype "passive"))
      (node (ref "T3") (pin "3") (pinfunction "3_3") (pintype "passive"))
    )
    (net (code "54") (name "/GE2_RXCLK") (class "Default")
      (node (ref "1") (pin "91") (pinfunction "GE2_RXCLK_91") (pintype "passive"))
      (node (ref "JP4") (pin "14") (pinfunction "14_14") (pintype "passive"))
    )
    (net (code "55") (name "/GE2_RXD0") (class "Default")
      (node (ref "1") (pin "89") (pinfunction "GE2_RXD0_89") (pintype "passive"))
      (node (ref "JP4") (pin "16") (pinfunction "16_16") (pintype "passive"))
    )
    (net (code "56") (name "/GE2_RXD1") (class "Default")
      (node (ref "1") (pin "88") (pinfunction "GE2_RXD1_88") (pintype "passive"))
      (node (ref "JP4") (pin "17") (pinfunction "17_17") (pintype "passive"))
    )
    (net (code "57") (name "/GE2_RXD2") (class "Default")
      (node (ref "1") (pin "87") (pinfunction "GE2_RXD2_87") (pintype "passive"))
      (node (ref "JP4") (pin "18") (pinfunction "18_18") (pintype "passive"))
    )
    (net (code "58") (name "/GE2_RXD3") (class "Default")
      (node (ref "1") (pin "86") (pinfunction "GE2_RXD3_86") (pintype "passive"))
      (node (ref "JP4") (pin "19") (pinfunction "19_19") (pintype "passive"))
    )
    (net (code "59") (name "/GE2_RXDV") (class "Default")
      (node (ref "1") (pin "90") (pinfunction "GE2_RXDV_90") (pintype "passive"))
      (node (ref "JP4") (pin "15") (pinfunction "15_15") (pintype "passive"))
    )
    (net (code "60") (name "/GE2_TXCLK") (class "Default")
      (node (ref "1") (pin "85") (pinfunction "GE2_TXCLK_85") (pintype "passive"))
      (node (ref "JP4") (pin "20") (pinfunction "20_20") (pintype "passive"))
    )
    (net (code "61") (name "/GE2_TXD0") (class "Default")
      (node (ref "1") (pin "80") (pinfunction "GE2_TXD0_80") (pintype "passive"))
      (node (ref "JP4") (pin "25") (pinfunction "25_25") (pintype "passive"))
    )
    (net (code "62") (name "/GE2_TXD1") (class "Default")
      (node (ref "1") (pin "79") (pinfunction "GE2_TXD1_79") (pintype "passive"))
      (node (ref "JP4") (pin "26") (pinfunction "26_26") (pintype "passive"))
    )
    (net (code "63") (name "/GE2_TXD2") (class "Default")
      (node (ref "1") (pin "78") (pinfunction "GE2_TXD2_78") (pintype "passive"))
      (node (ref "JP4") (pin "27") (pinfunction "27_27") (pintype "passive"))
    )
    (net (code "64") (name "/GE2_TXD3") (class "Default")
      (node (ref "1") (pin "77") (pinfunction "GE2_TXD3_77") (pintype "passive"))
      (node (ref "JP4") (pin "28") (pinfunction "28_28") (pintype "passive"))
    )
    (net (code "65") (name "/GE2_TXEN") (class "Default")
      (node (ref "1") (pin "84") (pinfunction "GE2_TXEN_84") (pintype "passive"))
      (node (ref "JP4") (pin "21") (pinfunction "21_21") (pintype "passive"))
    )
    (net (code "66") (name "/GPIO0") (class "Default")
      (node (ref "1") (pin "104") (pinfunction "GPIO0_104") (pintype "passive"))
      (node (ref "JP4") (pin "1") (pinfunction "1_1") (pintype "passive"))
    )
    (net (code "67") (name "/I2C_SCLK") (class "Default")
      (node (ref "1") (pin "96") (pinfunction "I2C_SCLK_96") (pintype "passive"))
      (node (ref "JP4") (pin "9") (pinfunction "9_9") (pintype "passive"))
    )
    (net (code "68") (name "/I2C_SD") (class "Default")
      (node (ref "1") (pin "97") (pinfunction "I2C_SD_97") (pintype "passive"))
      (node (ref "JP4") (pin "8") (pinfunction "8_8") (pintype "passive"))
    )
    (net (code "69") (name "/JTCLK") (class "Default")
      (node (ref "1") (pin "124") (pinfunction "JTCLK_124") (pintype "passive"))
      (node (ref "JP3") (pin "18") (pinfunction "18_18") (pintype "passive"))
    )
    (net (code "70") (name "/JTDI") (class "Default")
      (node (ref "1") (pin "122") (pinfunction "JTDI_122") (pintype "passive"))
      (node (ref "JP3") (pin "20") (pinfunction "20_20") (pintype "passive"))
    )
    (net (code "71") (name "/JTDO") (class "Default")
      (node (ref "1") (pin "121") (pinfunction "JTDO_121") (pintype "passive"))
      (node (ref "D9") (pin "2") (pinfunction "2_2") (pintype "passive"))
      (node (ref "JP3") (pin "19") (pinfunction "19_19") (pintype "passive"))
    )
    (net (code "72") (name "/JTMS") (class "Default")
      (node (ref "1") (pin "120") (pinfunction "JTMS_120") (pintype "passive"))
      (node (ref "JP3") (pin "22") (pinfunction "22_22") (pintype "passive"))
    )
    (net (code "73") (name "/JTRST_N") (class "Default")
      (node (ref "1") (pin "123") (pinfunction "JTRST_N_123") (pintype "passive"))
      (node (ref "JP3") (pin "17") (pinfunction "17_17") (pintype "passive"))
    )
    (net (code "74") (name "/LED_WLAN_SOCKET") (class "Default")
      (node (ref "D8") (pin "1") (pinfunction "2_1") (pintype "passive"))
      (node (ref "J1") (pin "44") (pinfunction "44_44") (pintype "passive"))
      (node (ref "R16") (pin "2") (pinfunction "2_2") (pintype "passive"))
    )
    (net (code "75") (name "/MDC") (class "Default")
      (node (ref "1") (pin "83") (pinfunction "MDC_83") (pintype "passive"))
      (node (ref "JP4") (pin "22") (pinfunction "22_22") (pintype "passive"))
    )
    (net (code "76") (name "/MDIO") (class "Default")
      (node (ref "1") (pin "82") (pinfunction "MDIO_82") (pintype "passive"))
      (node (ref "JP4") (pin "23") (pinfunction "23_23") (pintype "passive"))
    )
    (net (code "77") (name "/ND_ALE") (class "Default")
      (node (ref "1") (pin "138") (pinfunction "ND_ALE_138") (pintype "passive"))
      (node (ref "JP3") (pin "4") (pinfunction "4_4") (pintype "passive"))
    )
    (net (code "78") (name "/ND_CLE") (class "Default")
      (node (ref "1") (pin "137") (pinfunction "ND_CLE_137") (pintype "passive"))
      (node (ref "JP3") (pin "3") (pinfunction "3_3") (pintype "passive"))
    )
    (net (code "79") (name "/ND_CS_N") (class "Default")
      (node (ref "1") (pin "136") (pinfunction "ND_CS_N_136") (pintype "passive"))
      (node (ref "JP3") (pin "6") (pinfunction "6_6") (pintype "passive"))
    )
    (net (code "80") (name "/ND_D0") (class "Default")
      (node (ref "1") (pin "133") (pinfunction "ND_D0_133") (pintype "passive"))
      (node (ref "JP3") (pin "7") (pinfunction "7_7") (pintype "passive"))
    )
    (net (code "81") (name "/ND_D1") (class "Default")
      (node (ref "1") (pin "132") (pinfunction "ND_D1_132") (pintype "passive"))
      (node (ref "JP3") (pin "10") (pinfunction "10_10") (pintype "passive"))
    )
    (net (code "82") (name "/ND_D2") (class "Default")
      (node (ref "1") (pin "131") (pinfunction "ND_D2_131") (pintype "passive"))
      (node (ref "JP3") (pin "9") (pinfunction "9_9") (pintype "passive"))
    )
    (net (code "83") (name "/ND_D3") (class "Default")
      (node (ref "1") (pin "130") (pinfunction "ND_D3_130") (pintype "passive"))
      (node (ref "JP3") (pin "12") (pinfunction "12_12") (pintype "passive"))
    )
    (net (code "84") (name "/ND_D4") (class "Default")
      (node (ref "1") (pin "129") (pinfunction "ND_D4_129") (pintype "passive"))
      (node (ref "JP3") (pin "11") (pinfunction "11_11") (pintype "passive"))
    )
    (net (code "85") (name "/ND_D5") (class "Default")
      (node (ref "1") (pin "128") (pinfunction "ND_D5_128") (pintype "passive"))
      (node (ref "JP3") (pin "14") (pinfunction "14_14") (pintype "passive"))
    )
    (net (code "86") (name "/ND_D6") (class "Default")
      (node (ref "1") (pin "127") (pinfunction "ND_D6_127") (pintype "passive"))
      (node (ref "JP3") (pin "13") (pinfunction "13_13") (pintype "passive"))
    )
    (net (code "87") (name "/ND_D7") (class "Default")
      (node (ref "1") (pin "126") (pinfunction "ND_D7_126") (pintype "passive"))
      (node (ref "JP3") (pin "16") (pinfunction "16_16") (pintype "passive"))
    )
    (net (code "88") (name "/ND_RB_N") (class "Default")
      (node (ref "1") (pin "134") (pinfunction "ND_RB_N_134") (pintype "passive"))
      (node (ref "JP3") (pin "8") (pinfunction "8_8") (pintype "passive"))
    )
    (net (code "89") (name "/ND_RE_N") (class "Default")
      (node (ref "1") (pin "135") (pinfunction "ND_RE_N_135") (pintype "passive"))
      (node (ref "JP3") (pin "5") (pinfunction "5_5") (pintype "passive"))
    )
    (net (code "90") (name "/ND_WE_N") (class "Default")
      (node (ref "1") (pin "139") (pinfunction "ND_WE_N_139") (pintype "passive"))
      (node (ref "JP3") (pin "1") (pinfunction "1_1") (pintype "passive"))
    )
    (net (code "91") (name "/ND_WP") (class "Default")
      (node (ref "1") (pin "140") (pinfunction "ND_WP_140") (pintype "passive"))
      (node (ref "JP3") (pin "2") (pinfunction "2_2") (pintype "passive"))
    )
    (net (code "92") (name "/PCIE0_5V") (class "Default")
      (node (ref "C24") (pin "1") (pinfunction "1_1") (pintype "passive"))
      (node (ref "C25") (pin "1") (pinfunction "1_1") (pintype "passive"))
      (node (ref "J1") (pin "47") (pinfunction "47_47") (pintype "passive"))
      (node (ref "J1") (pin "49") (pinfunction "49_49") (pintype "passive"))
      (node (ref "R17") (pin "1") (pinfunction "1_1") (pintype "passive"))
    )
    (net (code "93") (name "/PCIE_CKN0") (class "Default")
      (node (ref "1") (pin "118") (pinfunction "PCIE_CKN0_118") (pintype "passive"))
      (node (ref "JP3") (pin "24") (pinfunction "24_24") (pintype "passive"))
    )
    (net (code "94") (name "/PCIE_CKN1") (class "Default")
      (node (ref "1") (pin "110") (pinfunction "PCIE_CKN1_110") (pintype "passive"))
      (node (ref "JP3") (pin "30") (pinfunction "30_30") (pintype "passive"))
    )
    (net (code "95") (name "/PCIE_CKN2") (class "Default")
      (node (ref "1") (pin "102") (pinfunction "PCIE_CKN2_102") (pintype "passive"))
      (node (ref "J1") (pin "11") (pinfunction "11_11") (pintype "passive"))
      (node (ref "JP4") (pin "3") (pinfunction "3_3") (pintype "passive"))
    )
    (net (code "96") (name "/PCIE_CKP0") (class "Default")
      (node (ref "1") (pin "117") (pinfunction "PCIE_CKP0_117") (pintype "passive"))
      (node (ref "JP3") (pin "23") (pinfunction "23_23") (pintype "passive"))
    )
    (net (code "97") (name "/PCIE_CKP1") (class "Default")
      (node (ref "1") (pin "111") (pinfunction "PCIE_CKP1_111") (pintype "passive"))
      (node (ref "JP3") (pin "29") (pinfunction "29_29") (pintype "passive"))
    )
    (net (code "98") (name "/PCIE_CKP2") (class "Default")
      (node (ref "1") (pin "103") (pinfunction "PCIE_CKP2_103") (pintype "passive"))
      (node (ref "J1") (pin "13") (pinfunction "13_13") (pintype "passive"))
      (node (ref "JP4") (pin "2") (pinfunction "2_2") (pintype "passive"))
    )
    (net (code "99") (name "/PCIE_RXN0") (class "Default")
      (node (ref "1") (pin "114") (pinfunction "PCIE_RXN0_114") (pintype "passive"))
      (node (ref "JP3") (pin "28") (pinfunction "28_28") (pintype "passive"))
    )
    (net (code "100") (name "/PCIE_RXN1") (class "Default")
      (node (ref "1") (pin "109") (pinfunction "PCIE_RXN1_109") (pintype "passive"))
      (node (ref "JP3") (pin "31") (pinfunction "31_31") (pintype "passive"))
    )
    (net (code "101") (name "/PCIE_RXN2") (class "Default")
      (node (ref "1") (pin "100") (pinfunction "PCIE_RXN2_100") (pintype "passive"))
      (node (ref "J1") (pin "25") (pinfunction "25_25") (pintype "passive"))
      (node (ref "JP4") (pin "5") (pinfunction "5_5") (pintype "passive"))
    )
    (net (code "102") (name "/PCIE_RXP0") (class "Default")
      (node (ref "1") (pin "113") (pinfunction "PCIE_RXP0_113") (pintype "passive"))
      (node (ref "JP3") (pin "27") (pinfunction "27_27") (pintype "passive"))
    )
    (net (code "103") (name "/PCIE_RXP1") (class "Default")
      (node (ref "1") (pin "108") (pinfunction "PCIE_RXP1_108") (pintype "passive"))
      (node (ref "JP3") (pin "32") (pinfunction "32_32") (pintype "passive"))
    )
    (net (code "104") (name "/PCIE_RXP2") (class "Default")
      (node (ref "1") (pin "101") (pinfunction "PCIE_RXP2_101") (pintype "passive"))
      (node (ref "J1") (pin "23") (pinfunction "23_23") (pintype "passive"))
      (node (ref "JP4") (pin "4") (pinfunction "4_4") (pintype "passive"))
    )
    (net (code "105") (name "/PCIE_TXN0") (class "Default")
      (node (ref "1") (pin "115") (pinfunction "PCIE_TXN0_115") (pintype "passive"))
      (node (ref "JP3") (pin "25") (pinfunction "25_25") (pintype "passive"))
    )
    (net (code "106") (name "/PCIE_TXN1") (class "Default")
      (node (ref "1") (pin "107") (pinfunction "PCIE_TXN1_107") (pintype "passive"))
      (node (ref "JP3") (pin "33") (pinfunction "33_33") (pintype "passive"))
    )
    (net (code "107") (name "/PCIE_TXN2") (class "Default")
      (node (ref "1") (pin "98") (pinfunction "PCIE_TXN2_98") (pintype "passive"))
      (node (ref "J1") (pin "33") (pinfunction "33_33") (pintype "passive"))
      (node (ref "JP4") (pin "7") (pinfunction "7_7") (pintype "passive"))
    )
    (net (code "108") (name "/PCIE_TXP0") (class "Default")
      (node (ref "1") (pin "116") (pinfunction "PCIE_TXP0_116") (pintype "passive"))
      (node (ref "JP3") (pin "26") (pinfunction "26_26") (pintype "passive"))
    )
    (net (code "109") (name "/PCIE_TXP1") (class "Default")
      (node (ref "1") (pin "106") (pinfunction "PCIE_TXP1_106") (pintype "passive"))
      (node (ref "JP3") (pin "34") (pinfunction "34_34") (pintype "passive"))
    )
    (net (code "110") (name "/PCIE_TXP2") (class "Default")
      (node (ref "1") (pin "99") (pinfunction "PCIE_TXP2_99") (pintype "passive"))
      (node (ref "J1") (pin "31") (pinfunction "31_31") (pintype "passive"))
      (node (ref "JP4") (pin "6") (pinfunction "6_6") (pintype "passive"))
    )
    (net (code "111") (name "/PERST_N") (class "Default")
      (node (ref "1") (pin "105") (pinfunction "PERST_N_105") (pintype "passive"))
      (node (ref "J1") (pin "22") (pinfunction "22_22") (pintype "passive"))
    )
    (net (code "112") (name "/PORST_N") (class "Default")
      (node (ref "1") (pin "95") (pinfunction "PORST_N_95") (pintype "passive"))
      (node (ref "JP4") (pin "10") (pinfunction "10_10") (pintype "passive"))
    )
    (net (code "113") (name "/RTS2_N") (class "Default")
      (node (ref "1") (pin "14") (pinfunction "RTS2_N_14") (pintype "passive"))
      (node (ref "JP2") (pin "3") (pinfunction "3_3") (pintype "passive"))
    )
    (net (code "114") (name "/RTS3_N") (class "Default")
      (node (ref "1") (pin "16") (pinfunction "RTS3_N_16") (pintype "passive"))
      (node (ref "JP2") (pin "1") (pinfunction "1_1") (pintype "passive"))
    )
    (net (code "115") (name "/RX0_CH340") (class "Default")
      (node (ref "JP1") (pin "1") (pinfunction "1_1") (pintype "passive"))
      (node (ref "JP1") (pin "5") (pinfunction "5_5") (pintype "passive"))
      (node (ref "JP1") (pin "9") (pinfunction "9_9") (pintype "passive"))
      (node (ref "U5") (pin "9") (pinfunction "RXD_9") (pintype "passive"))
    )
    (net (code "116") (name "/RXD1") (class "Default")
      (node (ref "1") (pin "93") (pinfunction "RXD1_93") (pintype "passive"))
      (node (ref "JP1") (pin "4") (pinfunction "4_4") (pintype "passive"))
      (node (ref "JP4") (pin "12") (pinfunction "12_12") (pintype "passive"))
    )
    (net (code "117") (name "/RXD2") (class "Default")
      (node (ref "1") (pin "11") (pinfunction "RXD2_11") (pintype "passive"))
      (node (ref "JP1") (pin "8") (pinfunction "8_8") (pintype "passive"))
    )
    (net (code "118") (name "/RXD3") (class "Default")
      (node (ref "1") (pin "13") (pinfunction "RXD3_13") (pintype "passive"))
      (node (ref "JP1") (pin "12") (pinfunction "12_12") (pintype "passive"))
    )
    (net (code "119") (name "/SSUSB_RXN") (class "Default")
      (node (ref "1") (pin "23") (pinfunction "SSUSB_RXN_23") (pintype "passive"))
      (node (ref "J4") (pin "5") (pinfunction "5_5") (pintype "passive"))
    )
    (net (code "120") (name "/SSUSB_RXP") (class "Default")
      (node (ref "1") (pin "22") (pinfunction "SSUSB_RXP_22") (pintype "passive"))
      (node (ref "J4") (pin "6") (pinfunction "6_6") (pintype "passive"))
    )
    (net (code "121") (name "/SSUSB_TXN") (class "Default")
      (node (ref "1") (pin "21") (pinfunction "SSUSB_TXN_21") (pintype "passive"))
      (node (ref "J4") (pin "8") (pinfunction "8_8") (pintype "passive"))
    )
    (net (code "122") (name "/SSUSB_TXP") (class "Default")
      (node (ref "1") (pin "20") (pinfunction "SSUSB_TXP_20") (pintype "passive"))
      (node (ref "J4") (pin "9") (pinfunction "9_9") (pintype "passive"))
    )
    (net (code "123") (name "/TX0_CH340") (class "Default")
      (node (ref "JP1") (pin "11") (pinfunction "11_11") (pintype "passive"))
      (node (ref "JP1") (pin "3") (pinfunction "3_3") (pintype "passive"))
      (node (ref "JP1") (pin "7") (pinfunction "7_7") (pintype "passive"))
      (node (ref "R39") (pin "2") (pinfunction "2_2") (pintype "passive"))
    )
    (net (code "124") (name "/TXD1") (class "Default")
      (node (ref "1") (pin "94") (pinfunction "TXD1_94") (pintype "passive"))
      (node (ref "JP1") (pin "2") (pinfunction "2_2") (pintype "passive"))
      (node (ref "JP4") (pin "11") (pinfunction "11_11") (pintype "passive"))
    )
    (net (code "125") (name "/TXD2") (class "Default")
      (node (ref "1") (pin "10") (pinfunction "TXD2_10") (pintype "passive"))
      (node (ref "JP1") (pin "6") (pinfunction "6_6") (pintype "passive"))
    )
    (net (code "126") (name "/TXD3") (class "Default")
      (node (ref "1") (pin "12") (pinfunction "TXD3_12") (pintype "passive"))
      (node (ref "JP1") (pin "10") (pinfunction "10_10") (pintype "passive"))
    )
    (net (code "127") (name "/USB_DM_P0") (class "Default")
      (node (ref "1") (pin "26") (pinfunction "USB_DM_P0_26") (pintype "passive"))
      (node (ref "J4") (pin "2") (pinfunction "2_2") (pintype "passive"))
    )
    (net (code "128") (name "/USB_DM_P1") (class "Default")
      (node (ref "1") (pin "18") (pinfunction "USB_DM_1P_18") (pintype "passive"))
      (node (ref "J3") (pin "2") (pinfunction "2_2") (pintype "passive"))
      (node (ref "R48") (pin "2") (pinfunction "2_2") (pintype "passive"))
    )
    (net (code "129") (name "/USB_DP_P0") (class "Default")
      (node (ref "1") (pin "25") (pinfunction "USB_DP_P0_25") (pintype "passive"))
      (node (ref "J4") (pin "3") (pinfunction "3_3") (pintype "passive"))
    )
    (net (code "130") (name "/USB_DP_P1") (class "Default")
      (node (ref "1") (pin "17") (pinfunction "USB_DP_1P_17") (pintype "passive"))
      (node (ref "J3") (pin "3") (pinfunction "3_3") (pintype "passive"))
      (node (ref "R49") (pin "2") (pinfunction "2_2") (pintype "passive"))
    )
    (net (code "131") (name "/WDT_RST_N") (class "Default")
      (node (ref "1") (pin "112") (pinfunction "WDT_RST_N_112") (pintype "passive"))
      (node (ref "Default1") (pin "1") (pinfunction "1_1") (pintype "passive"))
    )
    (net (code "132") (name "3.3V") (class "Default")
      (node (ref "1") (pin "1") (pinfunction "3.3VD_1") (pintype "passive"))
      (node (ref "1") (pin "2") (pinfunction "3.3VD_2") (pintype "passive"))
      (node (ref "1") (pin "3") (pinfunction "3.3VD_3") (pintype "passive"))
      (node (ref "1") (pin "4") (pinfunction "3.3VD_4") (pintype "passive"))
      (node (ref "C13") (pin "1") (pinfunction "1_1") (pintype "passive"))
      (node (ref "C14") (pin "1") (pinfunction "1_1") (pintype "passive"))
      (node (ref "C20") (pin "1") (pinfunction "1_1") (pintype "passive"))
      (node (ref "C21") (pin "1") (pinfunction "1_1") (pintype "passive"))
      (node (ref "J1") (pin "2") (pinfunction "2_2") (pintype "passive"))
      (node (ref "J1") (pin "52") (pinfunction "52_52") (pintype "passive"))
      (node (ref "L2") (pin "2") (pinfunction "2_2") (pintype "passive"))
      (node (ref "R10") (pin "1") (pinfunction "1_1") (pintype "passive"))
      (node (ref "R15") (pin "2") (pinfunction "2_2") (pintype "passive"))
      (node (ref "R16") (pin "1") (pinfunction "1_1") (pintype "passive"))
      (node (ref "R40") (pin "1") (pinfunction "1_1") (pintype "passive"))
      (node (ref "R41") (pin "1") (pinfunction "1_1") (pintype "passive"))
      (node (ref "R43") (pin "1") (pinfunction "1_1") (pintype "passive"))
      (node (ref "R44") (pin "1") (pinfunction "1_1") (pintype "passive"))
      (node (ref "R45") (pin "1") (pinfunction "1_1") (pintype "passive"))
      (node (ref "R47") (pin "1") (pinfunction "1_1") (pintype "passive"))
    )
    (net (code "133") (name "5V") (class "Default")
      (node (ref "C49") (pin "2") (pinfunction "2_2") (pintype "passive"))
      (node (ref "D5") (pin "1") (pinfunction "1_1") (pintype "passive"))
      (node (ref "U4") (pin "3") (pinfunction "3_3") (pintype "passive"))
      (node (ref "USB1") (pin "1") (pinfunction "VCC_1") (pintype "passive"))
    )
    (net (code "134") (name "5VD") (class "Default")
      (node (ref "C10") (pin "1") (pinfunction "1_1") (pintype "passive"))
      (node (ref "C11") (pin "1") (pinfunction "1_1") (pintype "passive"))
      (node (ref "C12") (pin "1") (pinfunction "1_1") (pintype "passive"))
      (node (ref "C18") (pin "1") (pinfunction "1_1") (pintype "passive"))
      (node (ref "C19") (pin "1") (pinfunction "1_1") (pintype "passive"))
      (node (ref "C9") (pin "1") (pinfunction "1_1") (pintype "passive"))
      (node (ref "D5") (pin "2") (pinfunction "2_2") (pintype "passive"))
      (node (ref "J3") (pin "1") (pinfunction "1_1") (pintype "passive"))
      (node (ref "J4") (pin "1") (pinfunction "1_1") (pintype "passive"))
      (node (ref "L1") (pin "2") (pinfunction "2_2") (pintype "passive"))
      (node (ref "R1") (pin "1") (pinfunction "1_1") (pintype "passive"))
      (node (ref "R17") (pin "2") (pinfunction "2_2") (pintype "passive"))
      (node (ref "R18") (pin "1") (pinfunction "1_1") (pintype "passive"))
      (node (ref "R42") (pin "1") (pinfunction "1_1") (pintype "passive"))
    )
    (net (code "135") (name "12V") (class "Default")
      (node (ref "C15") (pin "1") (pinfunction "1_1") (pintype "passive"))
      (node (ref "C22") (pin "1") (pinfunction "1_1") (pintype "passive"))
      (node (ref "C48") (pin "1") (pinfunction "1_1") (pintype "passive"))
      (node (ref "C5") (pin "1") (pinfunction "1_1") (pintype "passive"))
      (node (ref "J2") (pin "1") (pinfunction "1_1") (pintype "power_in"))
      (node (ref "R14") (pin "2") (pinfunction "2_2") (pintype "passive"))
      (node (ref "R6") (pin "2") (pinfunction "2_2") (pintype "passive"))
      (node (ref "U1") (pin "3") (pinfunction "IN_3") (pintype "passive"))
      (node (ref "U3") (pin "3") (pinfunction "IN_3") (pintype "passive"))
    )
    (net (code "136") (name "GND") (class "Default")
      (node (ref "1") (pin "119") (pinfunction "GND_119") (pintype "passive"))
      (node (ref "1") (pin "125") (pinfunction "GND_125") (pintype "passive"))
      (node (ref "1") (pin "19") (pinfunction "GND_19") (pintype "passive"))
      (node (ref "1") (pin "24") (pinfunction "GND_24") (pintype "passive"))
      (node (ref "1") (pin "27") (pinfunction "GND_27") (pintype "passive"))
      (node (ref "1") (pin "44") (pinfunction "GND_44") (pintype "passive"))
      (node (ref "1") (pin "5") (pinfunction "GND_5") (pintype "passive"))
      (node (ref "1") (pin "53") (pinfunction "GND_53") (pintype "passive"))
      (node (ref "1") (pin "6") (pinfunction "GND_6") (pintype "passive"))
      (node (ref "1") (pin "62") (pinfunction "GND_62") (pintype "passive"))
      (node (ref "1") (pin "7") (pinfunction "GND_7") (pintype "passive"))
      (node (ref "1") (pin "8") (pinfunction "GND_8") (pintype "passive"))
      (node (ref "1") (pin "92") (pinfunction "GND_92") (pintype "passive"))
      (node (ref "C10") (pin "2") (pinfunction "2_2") (pintype "passive"))
      (node (ref "C11") (pin "2") (pinfunction "2_2") (pintype "passive"))
      (node (ref "C12") (pin "2") (pinfunction "2_2") (pintype "passive"))
      (node (ref "C13") (pin "2") (pinfunction "2_2") (pintype "passive"))
      (node (ref "C14") (pin "2") (pinfunction "2_2") (pintype "passive"))
      (node (ref "C15") (pin "2") (pinfunction "2_2") (pintype "passive"))
      (node (ref "C18") (pin "2") (pinfunction "2_2") (pintype "passive"))
      (node (ref "C19") (pin "2") (pinfunction "2_2") (pintype "passive"))
      (node (ref "C20") (pin "2") (pinfunction "2_2") (pintype "passive"))
      (node (ref "C21") (pin "2") (pinfunction "2_2") (pintype "passive"))
      (node (ref "C22") (pin "2") (pinfunction "2_2") (pintype "passive"))
      (node (ref "C23") (pin "2") (pinfunction "2_2") (pintype "passive"))
      (node (ref "C24") (pin "2") (pinfunction "2_2") (pintype "passive"))
      (node (ref "C25") (pin "2") (pinfunction "2_2") (pintype "passive"))
      (node (ref "C26") (pin "2") (pinfunction "2_2") (pintype "passive"))
      (node (ref "C27") (pin "1") (pinfunction "1_1") (pintype "passive"))
      (node (ref "C28") (pin "1") (pinfunction "1_1") (pintype "passive"))
      (node (ref "C29") (pin "1") (pinfunction "1_1") (pintype "passive"))
      (node (ref "C30") (pin "1") (pinfunction "1_1") (pintype "passive"))
      (node (ref "C31") (pin "1") (pinfunction "1_1") (pintype "passive"))
      (node (ref "C32") (pin "1") (pinfunction "1_1") (pintype "passive"))
      (node (ref "C33") (pin "1") (pinfunction "1_1") (pintype "passive"))
      (node (ref "C34") (pin "1") (pinfunction "1_1") (pintype "passive"))
      (node (ref "C35") (pin "1") (pinfunction "1_1") (pintype "passive"))
      (node (ref "C36") (pin "1") (pinfunction "1_1") (pintype "passive"))
      (node (ref "C37") (pin "1") (pinfunction "1_1") (pintype "passive"))
      (node (ref "C38") (pin "1") (pinfunction "1_1") (pintype "passive"))
      (node (ref "C39") (pin "1") (pinfunction "1_1") (pintype "passive"))
      (node (ref "C4") (pin "2") (pinfunction "2_2") (pintype "passive"))
      (node (ref "C40") (pin "1") (pinfunction "1_1") (pintype "passive"))
      (node (ref "C41") (pin "1") (pinfunction "1_1") (pintype "passive"))
      (node (ref "C42") (pin "1") (pinfunction "1_1") (pintype "passive"))
      (node (ref "C43") (pin "1") (pinfunction "1_1") (pintype "passive"))
      (node (ref "C44") (pin "1") (pinfunction "1_1") (pintype "passive"))
      (node (ref "C45") (pin "1") (pinfunction "1_1") (pintype "passive"))
      (node (ref "C46") (pin "1") (pinfunction "1_1") (pintype "passive"))
      (node (ref "C47") (pin "2") (pinfunction "2_2") (pintype "passive"))
      (node (ref "C48") (pin "2") (pinfunction "2_2") (pintype "passive"))
      (node (ref "C49") (pin "1") (pinfunction "1_1") (pintype "passive"))
      (node (ref "C5") (pin "2") (pinfunction "2_2") (pintype "passive"))
      (node (ref "C7") (pin "2") (pinfunction "2_2") (pintype "passive"))
      (node (ref "C9") (pin "2") (pinfunction "2_2") (pintype "passive"))
      (node (ref "D6") (pin "2") (pinfunction "2_2") (pintype "passive"))
      (node (ref "D7") (pin "2") (pinfunction "2_2") (pintype "passive"))
      (node (ref "Default1") (pin "2") (pinfunction "2_2") (pintype "passive"))
      (node (ref "Default1") (pin "3") (pinfunction "3_3") (pintype "passive"))
      (node (ref "J1") (pin "15") (pinfunction "15_15") (pintype "passive"))
      (node (ref "J1") (pin "18") (pinfunction "18_18") (pintype "passive"))
      (node (ref "J1") (pin "21") (pinfunction "21_21") (pintype "passive"))
      (node (ref "J1") (pin "26") (pinfunction "26_26") (pintype "passive"))
      (node (ref "J1") (pin "27") (pinfunction "27_27") (pintype "passive"))
      (node (ref "J1") (pin "29") (pinfunction "29_29") (pintype "passive"))
      (node (ref "J1") (pin "34") (pinfunction "34_34") (pintype "passive"))
      (node (ref "J1") (pin "35") (pinfunction "35_35") (pintype "passive"))
      (node (ref "J1") (pin "37") (pinfunction "37_37") (pintype "passive"))
      (node (ref "J1") (pin "4") (pinfunction "4_4") (pintype "passive"))
      (node (ref "J1") (pin "40") (pinfunction "40_40") (pintype "passive"))
      (node (ref "J1") (pin "43") (pinfunction "43_43") (pintype "passive"))
      (node (ref "J1") (pin "50") (pinfunction "50_50") (pintype "passive"))
      (node (ref "J1") (pin "55") (pinfunction "53_55") (pintype "passive"))
      (node (ref "J1") (pin "56") (pinfunction "54_56") (pintype "passive"))
      (node (ref "J1") (pin "57") (pinfunction "57_57") (pintype "passive"))
      (node (ref "J1") (pin "58") (pinfunction "58_58") (pintype "passive"))
      (node (ref "J1") (pin "59") (pinfunction "59_59") (pintype "passive"))
      (node (ref "J1") (pin "60") (pinfunction "60_60") (pintype "passive"))
      (node (ref "J1") (pin "63") (pinfunction "63_63") (pintype "passive"))
      (node (ref "J1") (pin "64") (pinfunction "64_64") (pintype "passive"))
      (node (ref "J1") (pin "65") (pinfunction "65_65") (pintype "passive"))
      (node (ref "J1") (pin "66") (pinfunction "66_66") (pintype "passive"))
      (node (ref "J1") (pin "9") (pinfunction "9_9") (pintype "passive"))
      (node (ref "J2") (pin "2") (pinfunction "2_2") (pintype "power_in"))
      (node (ref "J2") (pin "3") (pinfunction "3_3") (pintype "power_in"))
      (node (ref "J3") (pin "4") (pinfunction "4_4") (pintype "passive"))
      (node (ref "J3") (pin "5") (pinfunction "5_5") (pintype "passive"))
      (node (ref "J3") (pin "6") (pinfunction "6_6") (pintype "passive"))
      (node (ref "J3") (pin "7") (pinfunction "7_7") (pintype "passive"))
      (node (ref "J3") (pin "8") (pinfunction "8_8") (pintype "passive"))
      (node (ref "J4") (pin "10") (pinfunction "10_10") (pintype "passive"))
      (node (ref "J4") (pin "11") (pinfunction "11_11") (pintype "passive"))
      (node (ref "J4") (pin "4") (pinfunction "4_4") (pintype "passive"))
      (node (ref "J4") (pin "7") (pinfunction "7_7") (pintype "passive"))
      (node (ref "JP3") (pin "15") (pinfunction "15_15") (pintype "passive"))
      (node (ref "JP3") (pin "21") (pinfunction "21_21") (pintype "passive"))
      (node (ref "JP4") (pin "13") (pinfunction "13_13") (pintype "passive"))
      (node (ref "R11") (pin "1") (pinfunction "1_1") (pintype "passive"))
      (node (ref "R4") (pin "1") (pinfunction "1_1") (pintype "passive"))
      (node (ref "R46") (pin "1") (pinfunction "1_1") (pintype "passive"))
      (node (ref "U1") (pin "1") (pinfunction "GND_1") (pintype "passive"))
      (node (ref "U3") (pin "1") (pinfunction "GND_1") (pintype "passive"))
      (node (ref "U4") (pin "1") (pinfunction "1_1") (pintype "passive"))
      (node (ref "U5") (pin "3") (pinfunction "GND_3") (pintype "passive"))
      (node (ref "USB1") (pin "5") (pinfunction "GND_5") (pintype "passive"))
      (node (ref "USB1") (pin "6") (pinfunction "Hold_6") (pintype "passive"))
      (node (ref "USB1") (pin "7") (pinfunction "Hold_7") (pintype "passive"))
      (node (ref "USB1") (pin "8") (pinfunction "Hold_8") (pintype "passive"))
      (node (ref "USB1") (pin "9") (pinfunction "Hold_9") (pintype "passive"))
      (node (ref "W1") (pin "10") (pinfunction "10_10") (pintype "passive"))
    )
    (net (code "137") (name "LDO-3.3V") (class "Default")
      (node (ref "C4") (pin "1") (pinfunction "1_1") (pintype "passive"))
      (node (ref "C7") (pin "1") (pinfunction "1_1") (pintype "passive"))
      (node (ref "U4") (pin "0") (pinfunction "0_0") (pintype "passive"))
      (node (ref "U5") (pin "10") (pinfunction "3.3V_10") (pintype "passive"))
      (node (ref "U5") (pin "7") (pinfunction "VCC_7") (pintype "passive"))
    )
    (net (code "138") (name "Net-(C23-Pad1)") (class "Default")
      (node (ref "C23") (pin "1") (pinfunction "1_1") (pintype "passive"))
      (node (ref "C47") (pin "1") (pinfunction "1_1") (pintype "passive"))
      (node (ref "R19") (pin "1") (pinfunction "1_1") (pintype "passive"))
      (node (ref "R20") (pin "1") (pinfunction "1_1") (pintype "passive"))
      (node (ref "R21") (pin "1") (pinfunction "1_1") (pintype "passive"))
      (node (ref "R22") (pin "1") (pinfunction "1_1") (pintype "passive"))
      (node (ref "R23") (pin "1") (pinfunction "1_1") (pintype "passive"))
      (node (ref "R24") (pin "1") (pinfunction "1_1") (pintype "passive"))
      (node (ref "R25") (pin "1") (pinfunction "1_1") (pintype "passive"))
      (node (ref "R26") (pin "1") (pinfunction "1_1") (pintype "passive"))
      (node (ref "R27") (pin "1") (pinfunction "1_1") (pintype "passive"))
      (node (ref "R28") (pin "1") (pinfunction "1_1") (pintype "passive"))
      (node (ref "R29") (pin "1") (pinfunction "1_1") (pintype "passive"))
      (node (ref "R30") (pin "1") (pinfunction "1_1") (pintype "passive"))
      (node (ref "R31") (pin "1") (pinfunction "1_1") (pintype "passive"))
      (node (ref "R32") (pin "1") (pinfunction "1_1") (pintype "passive"))
      (node (ref "R33") (pin "1") (pinfunction "1_1") (pintype "passive"))
      (node (ref "R34") (pin "1") (pinfunction "1_1") (pintype "passive"))
      (node (ref "R35") (pin "1") (pinfunction "1_1") (pintype "passive"))
      (node (ref "R36") (pin "1") (pinfunction "1_1") (pintype "passive"))
      (node (ref "R37") (pin "1") (pinfunction "1_1") (pintype "passive"))
      (node (ref "R38") (pin "1") (pinfunction "1_1") (pintype "passive"))
    )
    (net (code "139") (name "Net-(C27-Pad2)") (class "Default")
      (node (ref "C27") (pin "2") (pinfunction "2_2") (pintype "passive"))
      (node (ref "T1") (pin "22") (pinfunction "22_22") (pintype "passive"))
    )
    (net (code "140") (name "Net-(C28-Pad2)") (class "Default")
      (node (ref "C28") (pin "2") (pinfunction "2_2") (pintype "passive"))
      (node (ref "T1") (pin "19") (pinfunction "19_19") (pintype "passive"))
    )
    (net (code "141") (name "Net-(C29-Pad2)") (class "Default")
      (node (ref "C29") (pin "2") (pinfunction "2_2") (pintype "passive"))
      (node (ref "T1") (pin "16") (pinfunction "16_16") (pintype "passive"))
    )
    (net (code "142") (name "Net-(C30-Pad2)") (class "Default")
      (node (ref "C30") (pin "2") (pinfunction "2_2") (pintype "passive"))
      (node (ref "T1") (pin "13") (pinfunction "13_13") (pintype "passive"))
    )
    (net (code "143") (name "Net-(C31-Pad2)") (class "Default")
      (node (ref "C31") (pin "2") (pinfunction "2_2") (pintype "passive"))
      (node (ref "T1") (pin "10") (pinfunction "10_10") (pintype "passive"))
    )
    (net (code "144") (name "Net-(C32-Pad2)") (class "Default")
      (node (ref "C32") (pin "2") (pinfunction "2_2") (pintype "passive"))
      (node (ref "T1") (pin "7") (pinfunction "7_7") (pintype "passive"))
    )
    (net (code "145") (name "Net-(C33-Pad2)") (class "Default")
      (node (ref "C33") (pin "2") (pinfunction "2_2") (pintype "passive"))
      (node (ref "T1") (pin "4") (pinfunction "4_4") (pintype "passive"))
    )
    (net (code "146") (name "Net-(C34-Pad2)") (class "Default")
      (node (ref "C34") (pin "2") (pinfunction "2_2") (pintype "passive"))
      (node (ref "T1") (pin "1") (pinfunction "1_1") (pintype "passive"))
    )
    (net (code "147") (name "Net-(C35-Pad2)") (class "Default")
      (node (ref "C35") (pin "2") (pinfunction "2_2") (pintype "passive"))
      (node (ref "T2") (pin "22") (pinfunction "22_22") (pintype "passive"))
    )
    (net (code "148") (name "Net-(C36-Pad2)") (class "Default")
      (node (ref "C36") (pin "2") (pinfunction "2_2") (pintype "passive"))
      (node (ref "T2") (pin "19") (pinfunction "19_19") (pintype "passive"))
    )
    (net (code "149") (name "Net-(C37-Pad2)") (class "Default")
      (node (ref "C37") (pin "2") (pinfunction "2_2") (pintype "passive"))
      (node (ref "T2") (pin "16") (pinfunction "16_16") (pintype "passive"))
    )
    (net (code "150") (name "Net-(C38-Pad2)") (class "Default")
      (node (ref "C38") (pin "2") (pinfunction "2_2") (pintype "passive"))
      (node (ref "T2") (pin "13") (pinfunction "13_13") (pintype "passive"))
    )
    (net (code "151") (name "Net-(C39-Pad2)") (class "Default")
      (node (ref "C39") (pin "2") (pinfunction "2_2") (pintype "passive"))
      (node (ref "T2") (pin "10") (pinfunction "10_10") (pintype "passive"))
    )
    (net (code "152") (name "Net-(C40-Pad2)") (class "Default")
      (node (ref "C40") (pin "2") (pinfunction "2_2") (pintype "passive"))
      (node (ref "T2") (pin "7") (pinfunction "7_7") (pintype "passive"))
    )
    (net (code "153") (name "Net-(C41-Pad2)") (class "Default")
      (node (ref "C41") (pin "2") (pinfunction "2_2") (pintype "passive"))
      (node (ref "T2") (pin "4") (pinfunction "4_4") (pintype "passive"))
    )
    (net (code "154") (name "Net-(C42-Pad2)") (class "Default")
      (node (ref "C42") (pin "2") (pinfunction "2_2") (pintype "passive"))
      (node (ref "T2") (pin "1") (pinfunction "1_1") (pintype "passive"))
    )
    (net (code "155") (name "Net-(C43-Pad2)") (class "Default")
      (node (ref "C43") (pin "2") (pinfunction "2_2") (pintype "passive"))
      (node (ref "T3") (pin "10") (pinfunction "10_10") (pintype "passive"))
    )
    (net (code "156") (name "Net-(C44-Pad2)") (class "Default")
      (node (ref "C44") (pin "2") (pinfunction "2_2") (pintype "passive"))
      (node (ref "T3") (pin "7") (pinfunction "7_7") (pintype "passive"))
    )
    (net (code "157") (name "Net-(C45-Pad2)") (class "Default")
      (node (ref "C45") (pin "2") (pinfunction "2_2") (pintype "passive"))
      (node (ref "T3") (pin "4") (pinfunction "4_4") (pintype "passive"))
    )
    (net (code "158") (name "Net-(C46-Pad2)") (class "Default")
      (node (ref "C46") (pin "2") (pinfunction "2_2") (pintype "passive"))
      (node (ref "T3") (pin "1") (pinfunction "1_1") (pintype "passive"))
    )
    (net (code "159") (name "Net-(D0-Pad1)") (class "Default")
      (node (ref "D0") (pin "1") (pinfunction "1_1") (pintype "passive"))
      (node (ref "R43") (pin "2") (pinfunction "2_2") (pintype "passive"))
    )
    (net (code "160") (name "Net-(D1-Pad1)") (class "Default")
      (node (ref "D1") (pin "1") (pinfunction "1_1") (pintype "passive"))
      (node (ref "R44") (pin "2") (pinfunction "2_2") (pintype "passive"))
    )
    (net (code "161") (name "Net-(D2-Pad1)") (class "Default")
      (node (ref "D2") (pin "1") (pinfunction "1_1") (pintype "passive"))
      (node (ref "R45") (pin "2") (pinfunction "2_2") (pintype "passive"))
    )
    (net (code "162") (name "Net-(D3-Pad2)") (class "Default")
      (node (ref "D3") (pin "2") (pinfunction "2_2") (pintype "passive"))
      (node (ref "R46") (pin "2") (pinfunction "2_2") (pintype "passive"))
    )
    (net (code "163") (name "Net-(D4-Pad1)") (class "Default")
      (node (ref "D4") (pin "1") (pinfunction "1_1") (pintype "passive"))
      (node (ref "R47") (pin "2") (pinfunction "2_2") (pintype "passive"))
    )
    (net (code "164") (name "Net-(D6-Pad1)") (class "Default")
      (node (ref "D6") (pin "1") (pinfunction "1_1") (pintype "passive"))
      (node (ref "R41") (pin "2") (pinfunction "2_2") (pintype "passive"))
    )
    (net (code "165") (name "Net-(D7-Pad1)") (class "Default")
      (node (ref "D7") (pin "1") (pinfunction "1_1") (pintype "passive"))
      (node (ref "R42") (pin "2") (pinfunction "2_2") (pintype "passive"))
    )
    (net (code "166") (name "Net-(D8-1)") (class "Default")
      (node (ref "D8") (pin "2") (pinfunction "1_2") (pintype "passive"))
      (node (ref "R15") (pin "1") (pinfunction "1_1") (pintype "passive"))
    )
    (net (code "167") (name "Net-(D9-Pad1)") (class "Default")
      (node (ref "D9") (pin "1") (pinfunction "1_1") (pintype "passive"))
      (node (ref "R40") (pin "2") (pinfunction "2_2") (pintype "passive"))
    )
    (net (code "168") (name "Net-(J1-Pad36)") (class "Default")
      (node (ref "J1") (pin "36") (pinfunction "36_36") (pintype "passive"))
      (node (ref "R48") (pin "1") (pinfunction "1_1") (pintype "passive"))
    )
    (net (code "169") (name "Net-(J1-Pad38)") (class "Default")
      (node (ref "J1") (pin "38") (pinfunction "38_38") (pintype "passive"))
      (node (ref "R49") (pin "1") (pinfunction "1_1") (pintype "passive"))
    )
    (net (code "170") (name "Net-(P1-Pad1)") (class "Default")
      (node (ref "P1") (pin "1") (pinfunction "1_1") (pintype "passive"))
      (node (ref "T1") (pin "25") (pinfunction "25_25") (pintype "passive"))
    )
    (net (code "171") (name "Net-(P1-Pad2)") (class "Default")
      (node (ref "P1") (pin "2") (pinfunction "2_2") (pintype "passive"))
      (node (ref "T1") (pin "26") (pinfunction "26_26") (pintype "passive"))
    )
    (net (code "172") (name "Net-(P1-Pad3)") (class "Default")
      (node (ref "P1") (pin "3") (pinfunction "3_3") (pintype "passive"))
      (node (ref "T1") (pin "28") (pinfunction "28_28") (pintype "passive"))
    )
    (net (code "173") (name "Net-(P1-Pad4)") (class "Default")
      (node (ref "P1") (pin "4") (pinfunction "4_4") (pintype "passive"))
      (node (ref "T1") (pin "31") (pinfunction "31_31") (pintype "passive"))
    )
    (net (code "174") (name "Net-(P1-Pad5)") (class "Default")
      (node (ref "P1") (pin "5") (pinfunction "5_5") (pintype "passive"))
      (node (ref "T1") (pin "32") (pinfunction "32_32") (pintype "passive"))
    )
    (net (code "175") (name "Net-(P1-Pad6)") (class "Default")
      (node (ref "P1") (pin "6") (pinfunction "6_6") (pintype "passive"))
      (node (ref "T1") (pin "29") (pinfunction "29_29") (pintype "passive"))
    )
    (net (code "176") (name "Net-(P1-Pad7)") (class "Default")
      (node (ref "P1") (pin "7") (pinfunction "7_7") (pintype "passive"))
      (node (ref "T1") (pin "34") (pinfunction "34_34") (pintype "passive"))
    )
    (net (code "177") (name "Net-(P1-Pad8)") (class "Default")
      (node (ref "P1") (pin "8") (pinfunction "8_8") (pintype "passive"))
      (node (ref "T1") (pin "35") (pinfunction "35_35") (pintype "passive"))
    )
    (net (code "178") (name "Net-(P1-Pad9)") (class "Default")
      (node (ref "P1") (pin "9") (pinfunction "9_9") (pintype "passive"))
      (node (ref "T1") (pin "37") (pinfunction "37_37") (pintype "passive"))
    )
    (net (code "179") (name "Net-(P1-Pad10)") (class "Default")
      (node (ref "P1") (pin "10") (pinfunction "10_10") (pintype "passive"))
      (node (ref "T1") (pin "38") (pinfunction "38_38") (pintype "passive"))
    )
    (net (code "180") (name "Net-(P1-Pad11)") (class "Default")
      (node (ref "P1") (pin "11") (pinfunction "11_11") (pintype "passive"))
      (node (ref "T1") (pin "40") (pinfunction "40_40") (pintype "passive"))
    )
    (net (code "181") (name "Net-(P1-Pad12)") (class "Default")
      (node (ref "P1") (pin "12") (pinfunction "12_12") (pintype "passive"))
      (node (ref "T1") (pin "43") (pinfunction "43_43") (pintype "passive"))
    )
    (net (code "182") (name "Net-(P1-Pad13)") (class "Default")
      (node (ref "P1") (pin "13") (pinfunction "13_13") (pintype "passive"))
      (node (ref "T1") (pin "44") (pinfunction "44_44") (pintype "passive"))
    )
    (net (code "183") (name "Net-(P1-Pad14)") (class "Default")
      (node (ref "P1") (pin "14") (pinfunction "14_14") (pintype "passive"))
      (node (ref "T1") (pin "41") (pinfunction "41_41") (pintype "passive"))
    )
    (net (code "184") (name "Net-(P1-Pad15)") (class "Default")
      (node (ref "P1") (pin "15") (pinfunction "15_15") (pintype "passive"))
      (node (ref "T1") (pin "46") (pinfunction "46_46") (pintype "passive"))
    )
    (net (code "185") (name "Net-(P1-Pad16)") (class "Default")
      (node (ref "P1") (pin "16") (pinfunction "16_16") (pintype "passive"))
      (node (ref "T1") (pin "47") (pinfunction "47_47") (pintype "passive"))
    )
    (net (code "186") (name "Net-(P1-Pad17)") (class "Default")
      (node (ref "P1") (pin "17") (pinfunction "17_17") (pintype "passive"))
      (node (ref "T2") (pin "25") (pinfunction "25_25") (pintype "passive"))
    )
    (net (code "187") (name "Net-(P1-Pad18)") (class "Default")
      (node (ref "P1") (pin "18") (pinfunction "18_18") (pintype "passive"))
      (node (ref "T2") (pin "26") (pinfunction "26_26") (pintype "passive"))
    )
    (net (code "188") (name "Net-(P1-Pad19)") (class "Default")
      (node (ref "P1") (pin "19") (pinfunction "19_19") (pintype "passive"))
      (node (ref "T2") (pin "28") (pinfunction "28_28") (pintype "passive"))
    )
    (net (code "189") (name "Net-(P1-Pad20)") (class "Default")
      (node (ref "P1") (pin "20") (pinfunction "20_20") (pintype "passive"))
      (node (ref "T2") (pin "31") (pinfunction "31_31") (pintype "passive"))
    )
    (net (code "190") (name "Net-(P1-Pad21)") (class "Default")
      (node (ref "P1") (pin "21") (pinfunction "21_21") (pintype "passive"))
      (node (ref "T2") (pin "32") (pinfunction "32_32") (pintype "passive"))
    )
    (net (code "191") (name "Net-(P1-Pad22)") (class "Default")
      (node (ref "P1") (pin "22") (pinfunction "22_22") (pintype "passive"))
      (node (ref "T2") (pin "29") (pinfunction "29_29") (pintype "passive"))
    )
    (net (code "192") (name "Net-(P1-Pad23)") (class "Default")
      (node (ref "P1") (pin "23") (pinfunction "23_23") (pintype "passive"))
      (node (ref "T2") (pin "34") (pinfunction "34_34") (pintype "passive"))
    )
    (net (code "193") (name "Net-(P1-Pad24)") (class "Default")
      (node (ref "P1") (pin "24") (pinfunction "24_24") (pintype "passive"))
      (node (ref "T2") (pin "35") (pinfunction "35_35") (pintype "passive"))
    )
    (net (code "194") (name "Net-(P1-Pad25)") (class "Default")
      (node (ref "P1") (pin "25") (pinfunction "25_25") (pintype "passive"))
      (node (ref "T2") (pin "37") (pinfunction "37_37") (pintype "passive"))
    )
    (net (code "195") (name "Net-(P1-Pad26)") (class "Default")
      (node (ref "P1") (pin "26") (pinfunction "26_26") (pintype "passive"))
      (node (ref "T2") (pin "38") (pinfunction "38_38") (pintype "passive"))
    )
    (net (code "196") (name "Net-(P1-Pad27)") (class "Default")
      (node (ref "P1") (pin "27") (pinfunction "27_27") (pintype "passive"))
      (node (ref "T2") (pin "40") (pinfunction "40_40") (pintype "passive"))
    )
    (net (code "197") (name "Net-(P1-Pad28)") (class "Default")
      (node (ref "P1") (pin "28") (pinfunction "28_28") (pintype "passive"))
      (node (ref "T2") (pin "43") (pinfunction "43_43") (pintype "passive"))
    )
    (net (code "198") (name "Net-(P1-Pad29)") (class "Default")
      (node (ref "P1") (pin "29") (pinfunction "29_29") (pintype "passive"))
      (node (ref "T2") (pin "44") (pinfunction "44_44") (pintype "passive"))
    )
    (net (code "199") (name "Net-(P1-Pad30)") (class "Default")
      (node (ref "P1") (pin "30") (pinfunction "30_30") (pintype "passive"))
      (node (ref "T2") (pin "41") (pinfunction "41_41") (pintype "passive"))
    )
    (net (code "200") (name "Net-(P1-Pad31)") (class "Default")
      (node (ref "P1") (pin "31") (pinfunction "31_31") (pintype "passive"))
      (node (ref "T2") (pin "46") (pinfunction "46_46") (pintype "passive"))
    )
    (net (code "201") (name "Net-(P1-Pad32)") (class "Default")
      (node (ref "P1") (pin "32") (pinfunction "32_32") (pintype "passive"))
      (node (ref "T2") (pin "47") (pinfunction "47_47") (pintype "passive"))
    )
    (net (code "202") (name "Net-(R1-Pad2)") (class "Default")
      (node (ref "R1") (pin "2") (pinfunction "2_2") (pintype "passive"))
      (node (ref "R2") (pin "1") (pinfunction "1_1") (pintype "passive"))
      (node (ref "R4") (pin "2") (pinfunction "2_2") (pintype "passive"))
    )
    (net (code "203") (name "Net-(R10-Pad2)") (class "Default")
      (node (ref "R10") (pin "2") (pinfunction "2_2") (pintype "passive"))
      (node (ref "R11") (pin "2") (pinfunction "2_2") (pintype "passive"))
      (node (ref "R9") (pin "1") (pinfunction "1_1") (pintype "passive"))
    )
    (net (code "204") (name "Net-(R19-Pad2)") (class "Default")
      (node (ref "R19") (pin "2") (pinfunction "2_2") (pintype "passive"))
      (node (ref "T1") (pin "27") (pinfunction "27_27") (pintype "passive"))
    )
    (net (code "205") (name "Net-(R20-Pad2)") (class "Default")
      (node (ref "R20") (pin "2") (pinfunction "2_2") (pintype "passive"))
      (node (ref "T1") (pin "30") (pinfunction "30_30") (pintype "passive"))
    )
    (net (code "206") (name "Net-(R21-Pad2)") (class "Default")
      (node (ref "R21") (pin "2") (pinfunction "2_2") (pintype "passive"))
      (node (ref "T1") (pin "33") (pinfunction "33_33") (pintype "passive"))
    )
    (net (code "207") (name "Net-(R22-Pad2)") (class "Default")
      (node (ref "R22") (pin "2") (pinfunction "2_2") (pintype "passive"))
      (node (ref "T1") (pin "36") (pinfunction "36_36") (pintype "passive"))
    )
    (net (code "208") (name "Net-(R23-Pad2)") (class "Default")
      (node (ref "R23") (pin "2") (pinfunction "2_2") (pintype "passive"))
      (node (ref "T1") (pin "39") (pinfunction "39_39") (pintype "passive"))
    )
    (net (code "209") (name "Net-(R24-Pad2)") (class "Default")
      (node (ref "R24") (pin "2") (pinfunction "2_2") (pintype "passive"))
      (node (ref "T1") (pin "42") (pinfunction "42_42") (pintype "passive"))
    )
    (net (code "210") (name "Net-(R25-Pad2)") (class "Default")
      (node (ref "R25") (pin "2") (pinfunction "2_2") (pintype "passive"))
      (node (ref "T1") (pin "45") (pinfunction "45_45") (pintype "passive"))
    )
    (net (code "211") (name "Net-(R26-Pad2)") (class "Default")
      (node (ref "R26") (pin "2") (pinfunction "2_2") (pintype "passive"))
      (node (ref "T1") (pin "48") (pinfunction "48_48") (pintype "passive"))
    )
    (net (code "212") (name "Net-(R27-Pad2)") (class "Default")
      (node (ref "R27") (pin "2") (pinfunction "2_2") (pintype "passive"))
      (node (ref "T2") (pin "27") (pinfunction "27_27") (pintype "passive"))
    )
    (net (code "213") (name "Net-(R28-Pad2)") (class "Default")
      (node (ref "R28") (pin "2") (pinfunction "2_2") (pintype "passive"))
      (node (ref "T2") (pin "30") (pinfunction "30_30") (pintype "passive"))
    )
    (net (code "214") (name "Net-(R29-Pad2)") (class "Default")
      (node (ref "R29") (pin "2") (pinfunction "2_2") (pintype "passive"))
      (node (ref "T2") (pin "33") (pinfunction "33_33") (pintype "passive"))
    )
    (net (code "215") (name "Net-(R30-Pad2)") (class "Default")
      (node (ref "R30") (pin "2") (pinfunction "2_2") (pintype "passive"))
      (node (ref "T2") (pin "36") (pinfunction "36_36") (pintype "passive"))
    )
    (net (code "216") (name "Net-(R31-Pad2)") (class "Default")
      (node (ref "R31") (pin "2") (pinfunction "2_2") (pintype "passive"))
      (node (ref "T2") (pin "39") (pinfunction "39_39") (pintype "passive"))
    )
    (net (code "217") (name "Net-(R32-Pad2)") (class "Default")
      (node (ref "R32") (pin "2") (pinfunction "2_2") (pintype "passive"))
      (node (ref "T2") (pin "42") (pinfunction "42_42") (pintype "passive"))
    )
    (net (code "218") (name "Net-(R33-Pad2)") (class "Default")
      (node (ref "R33") (pin "2") (pinfunction "2_2") (pintype "passive"))
      (node (ref "T2") (pin "45") (pinfunction "45_45") (pintype "passive"))
    )
    (net (code "219") (name "Net-(R34-Pad2)") (class "Default")
      (node (ref "R34") (pin "2") (pinfunction "2_2") (pintype "passive"))
      (node (ref "T2") (pin "48") (pinfunction "48_48") (pintype "passive"))
    )
    (net (code "220") (name "Net-(R35-Pad2)") (class "Default")
      (node (ref "R35") (pin "2") (pinfunction "2_2") (pintype "passive"))
      (node (ref "T3") (pin "15") (pinfunction "15_15") (pintype "passive"))
    )
    (net (code "221") (name "Net-(R36-Pad2)") (class "Default")
      (node (ref "R36") (pin "2") (pinfunction "2_2") (pintype "passive"))
      (node (ref "T3") (pin "18") (pinfunction "18_18") (pintype "passive"))
    )
    (net (code "222") (name "Net-(R37-Pad2)") (class "Default")
      (node (ref "R37") (pin "2") (pinfunction "2_2") (pintype "passive"))
      (node (ref "T3") (pin "21") (pinfunction "21_21") (pintype "passive"))
    )
    (net (code "223") (name "Net-(R38-Pad2)") (class "Default")
      (node (ref "R38") (pin "2") (pinfunction "2_2") (pintype "passive"))
      (node (ref "T3") (pin "24") (pinfunction "24_24") (pintype "passive"))
    )
    (net (code "224") (name "Net-(T3-Pad13)") (class "Default")
      (node (ref "T3") (pin "13") (pinfunction "13_13") (pintype "passive"))
      (node (ref "W1") (pin "1") (pinfunction "1_1") (pintype "passive"))
    )
    (net (code "225") (name "Net-(T3-Pad14)") (class "Default")
      (node (ref "T3") (pin "14") (pinfunction "14_14") (pintype "passive"))
      (node (ref "W1") (pin "2") (pinfunction "2_2") (pintype "passive"))
    )
    (net (code "226") (name "Net-(T3-Pad16)") (class "Default")
      (node (ref "T3") (pin "16") (pinfunction "16_16") (pintype "passive"))
      (node (ref "W1") (pin "3") (pinfunction "3_3") (pintype "passive"))
    )
    (net (code "227") (name "Net-(T3-Pad17)") (class "Default")
      (node (ref "T3") (pin "17") (pinfunction "17_17") (pintype "passive"))
      (node (ref "W1") (pin "6") (pinfunction "6_6") (pintype "passive"))
    )
    (net (code "228") (name "Net-(T3-Pad19)") (class "Default")
      (node (ref "T3") (pin "19") (pinfunction "19_19") (pintype "passive"))
      (node (ref "W1") (pin "4") (pinfunction "4_4") (pintype "passive"))
    )
    (net (code "229") (name "Net-(T3-Pad20)") (class "Default")
      (node (ref "T3") (pin "20") (pinfunction "20_20") (pintype "passive"))
      (node (ref "W1") (pin "5") (pinfunction "5_5") (pintype "passive"))
    )
    (net (code "230") (name "Net-(T3-Pad22)") (class "Default")
      (node (ref "T3") (pin "22") (pinfunction "22_22") (pintype "passive"))
      (node (ref "W1") (pin "7") (pinfunction "7_7") (pintype "passive"))
    )
    (net (code "231") (name "Net-(T3-Pad23)") (class "Default")
      (node (ref "T3") (pin "23") (pinfunction "23_23") (pintype "passive"))
      (node (ref "W1") (pin "8") (pinfunction "8_8") (pintype "passive"))
    )
    (net (code "232") (name "Net-(U1-BST)") (class "Default")
      (node (ref "C8") (pin "2") (pinfunction "2_2") (pintype "passive"))
      (node (ref "U1") (pin "6") (pinfunction "BST_6") (pintype "passive"))
    )
    (net (code "233") (name "Net-(U1-EN)") (class "Default")
      (node (ref "R6") (pin "1") (pinfunction "1_1") (pintype "passive"))
      (node (ref "U1") (pin "5") (pinfunction "EN_5") (pintype "passive"))
    )
    (net (code "234") (name "Net-(U1-FB)") (class "Default")
      (node (ref "R2") (pin "2") (pinfunction "2_2") (pintype "passive"))
      (node (ref "U1") (pin "4") (pinfunction "FB_4") (pintype "passive"))
    )
    (net (code "235") (name "Net-(U1-SW)") (class "Default")
      (node (ref "C8") (pin "1") (pinfunction "1_1") (pintype "passive"))
      (node (ref "L1") (pin "1") (pinfunction "1_1") (pintype "passive"))
      (node (ref "U1") (pin "2") (pinfunction "SW_2") (pintype "passive"))
    )
    (net (code "236") (name "Net-(U3-BST)") (class "Default")
      (node (ref "C17") (pin "2") (pinfunction "2_2") (pintype "passive"))
      (node (ref "U3") (pin "6") (pinfunction "BST_6") (pintype "passive"))
    )
    (net (code "237") (name "Net-(U3-EN)") (class "Default")
      (node (ref "R14") (pin "1") (pinfunction "1_1") (pintype "passive"))
      (node (ref "U3") (pin "5") (pinfunction "EN_5") (pintype "passive"))
    )
    (net (code "238") (name "Net-(U3-FB)") (class "Default")
      (node (ref "R9") (pin "2") (pinfunction "2_2") (pintype "passive"))
      (node (ref "U3") (pin "4") (pinfunction "FB_4") (pintype "passive"))
    )
    (net (code "239") (name "Net-(U3-SW)") (class "Default")
      (node (ref "C17") (pin "1") (pinfunction "1_1") (pintype "passive"))
      (node (ref "L2") (pin "1") (pinfunction "1_1") (pintype "passive"))
      (node (ref "U3") (pin "2") (pinfunction "SW_2") (pintype "passive"))
    )
    (net (code "240") (name "Net-(U5-TXD)") (class "Default")
      (node (ref "R39") (pin "1") (pinfunction "1_1") (pintype "passive"))
      (node (ref "U5") (pin "8") (pinfunction "TXD_8") (pintype "passive"))
    )
    (net (code "241") (name "unconnected-(J1-0-Pad1)") (class "Default")
      (node (ref "J1") (pin "1") (pinfunction "0_1") (pintype "passive"))
    )
    (net (code "242") (name "unconnected-(J1-Pad3)") (class "Default")
      (node (ref "J1") (pin "3") (pinfunction "3_3") (pintype "passive"))
    )
    (net (code "243") (name "unconnected-(J1-Pad5)") (class "Default")
      (node (ref "J1") (pin "5") (pinfunction "5_5") (pintype "passive"))
    )
    (net (code "244") (name "unconnected-(J1-Pad6)") (class "Default")
      (node (ref "J1") (pin "6") (pinfunction "6_6") (pintype "passive"))
    )
    (net (code "245") (name "unconnected-(J1-Pad7)") (class "Default")
      (node (ref "J1") (pin "7") (pinfunction "7_7") (pintype "passive"))
    )
    (net (code "246") (name "unconnected-(J1-Pad8)") (class "Default")
      (node (ref "J1") (pin "8") (pinfunction "8_8") (pintype "passive"))
    )
    (net (code "247") (name "unconnected-(J1-Pad10)") (class "Default")
      (node (ref "J1") (pin "10") (pinfunction "10_10") (pintype "passive"))
    )
    (net (code "248") (name "unconnected-(J1-Pad12)") (class "Default")
      (node (ref "J1") (pin "12") (pinfunction "12_12") (pintype "passive"))
    )
    (net (code "249") (name "unconnected-(J1-Pad14)") (class "Default")
      (node (ref "J1") (pin "14") (pinfunction "14_14") (pintype "passive"))
    )
    (net (code "250") (name "unconnected-(J1-Pad16)") (class "Default")
      (node (ref "J1") (pin "16") (pinfunction "16_16") (pintype "passive"))
    )
    (net (code "251") (name "unconnected-(J1-Pad17)") (class "Default")
      (node (ref "J1") (pin "17") (pinfunction "17_17") (pintype "passive"))
    )
    (net (code "252") (name "unconnected-(J1-Pad19)") (class "Default")
      (node (ref "J1") (pin "19") (pinfunction "19_19") (pintype "passive"))
    )
    (net (code "253") (name "unconnected-(J1-Pad20)") (class "Default")
      (node (ref "J1") (pin "20") (pinfunction "20_20") (pintype "passive"))
    )
    (net (code "254") (name "unconnected-(J1-Pad28)") (class "Default")
      (node (ref "J1") (pin "28") (pinfunction "28_28") (pintype "passive"))
    )
    (net (code "255") (name "unconnected-(J1-Pad30)") (class "Default")
      (node (ref "J1") (pin "30") (pinfunction "30_30") (pintype "passive"))
    )
    (net (code "256") (name "unconnected-(J1-Pad32)") (class "Default")
      (node (ref "J1") (pin "32") (pinfunction "32_32") (pintype "passive"))
    )
    (net (code "257") (name "unconnected-(J1-Pad45)") (class "Default")
      (node (ref "J1") (pin "45") (pinfunction "45_45") (pintype "passive"))
    )
    (net (code "258") (name "unconnected-(J1-Pad51)") (class "Default")
      (node (ref "J1") (pin "51") (pinfunction "51_51") (pintype "passive"))
    )
    (net (code "259") (name "unconnected-(J1-Pad53)") (class "Default")
      (node (ref "J1") (pin "53") (pinfunction "53_53") (pintype "passive"))
    )
    (net (code "260") (name "unconnected-(J1-Pad54)") (class "Default")
      (node (ref "J1") (pin "54") (pinfunction "54_54") (pintype "passive"))
    )
    (net (code "261") (name "unconnected-(J1-Pad61)") (class "Default")
      (node (ref "J1") (pin "61") (pinfunction "61_61") (pintype "passive"))
    )
    (net (code "262") (name "unconnected-(J1-Pad62)") (class "Default")
      (node (ref "J1") (pin "62") (pinfunction "62_62") (pintype "passive"))
    )
    (net (code "263") (name "unconnected-(J1-Pad67)") (class "Default")
      (node (ref "J1") (pin "67") (pinfunction "67_67") (pintype "passive"))
    )
    (net (code "264") (name "unconnected-(J1-Pad68)") (class "Default")
      (node (ref "J1") (pin "68") (pinfunction "68_68") (pintype "passive"))
    )
    (net (code "265") (name "unconnected-(P1-Pad33)") (class "Default")
      (node (ref "P1") (pin "33") (pinfunction "33_33") (pintype "passive"))
    )
    (net (code "266") (name "unconnected-(P1-Pad34)") (class "Default")
      (node (ref "P1") (pin "34") (pinfunction "34_34") (pintype "passive"))
    )
    (net (code "267") (name "unconnected-(U4-Pad2)") (class "Default")
      (node (ref "U4") (pin "2") (pinfunction "2_2") (pintype "passive"))
    )
    (net (code "268") (name "unconnected-(U5-CTS-Pad5)") (class "Default")
      (node (ref "U5") (pin "5") (pinfunction "CTS_5") (pintype "passive"))
    )
    (net (code "269") (name "unconnected-(U5-RTS-Pad4)") (class "Default")
      (node (ref "U5") (pin "4") (pinfunction "RTS_4") (pintype "passive"))
    )
    (net (code "270") (name "unconnected-(U5-TNOW-Pad6)") (class "Default")
      (node (ref "U5") (pin "6") (pinfunction "TNOW_6") (pintype "passive"))
    )
    (net (code "271") (name "unconnected-(USB1-ID-Pad4)") (class "Default")
      (node (ref "USB1") (pin "4") (pinfunction "ID_4") (pintype "passive"))
    )
    (net (code "272") (name "unconnected-(W1-Pad9)") (class "Default")
      (node (ref "W1") (pin "9") (pinfunction "9_9") (pintype "passive"))
    )
  )
)
